# Spectre-Analyzer-SCH_SH2__C.net
KiCad netlist of a schematic drawn in Altium Designer
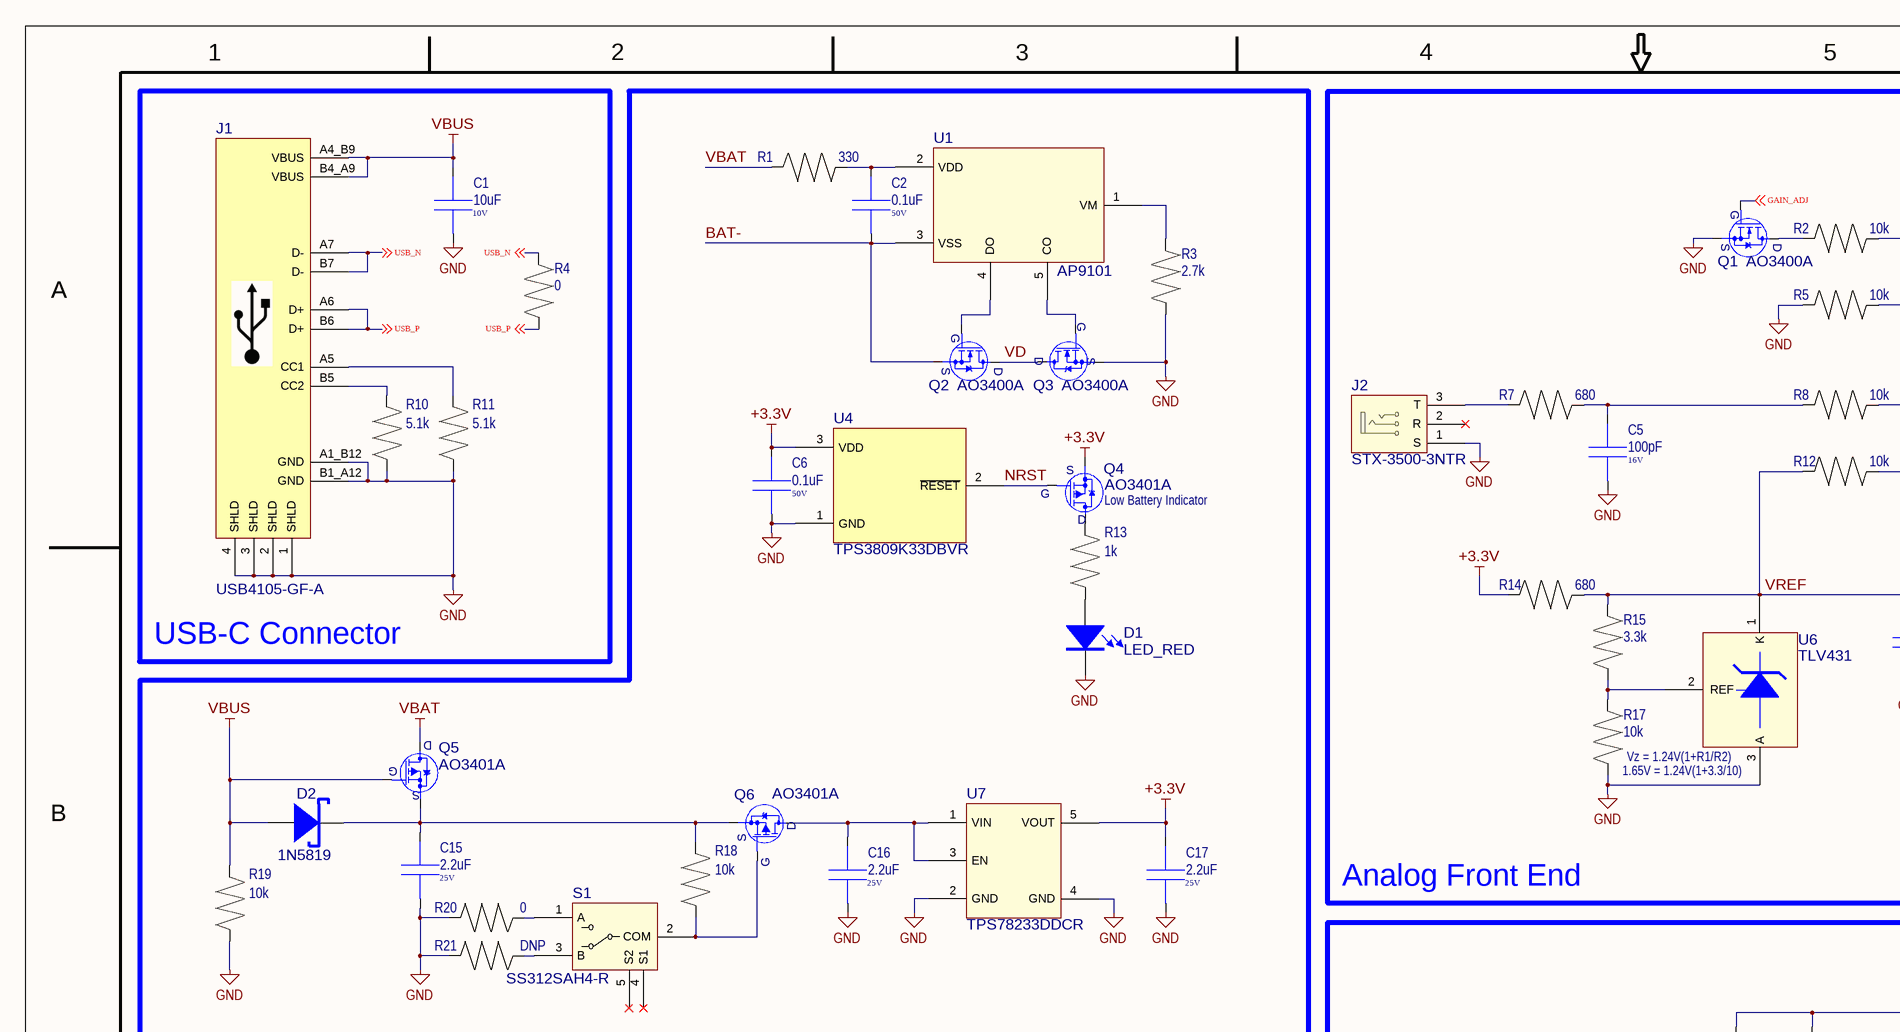
[diagram p0: Spectre-Analyzer-SCH_SH2_(C).SchDoc, top left]
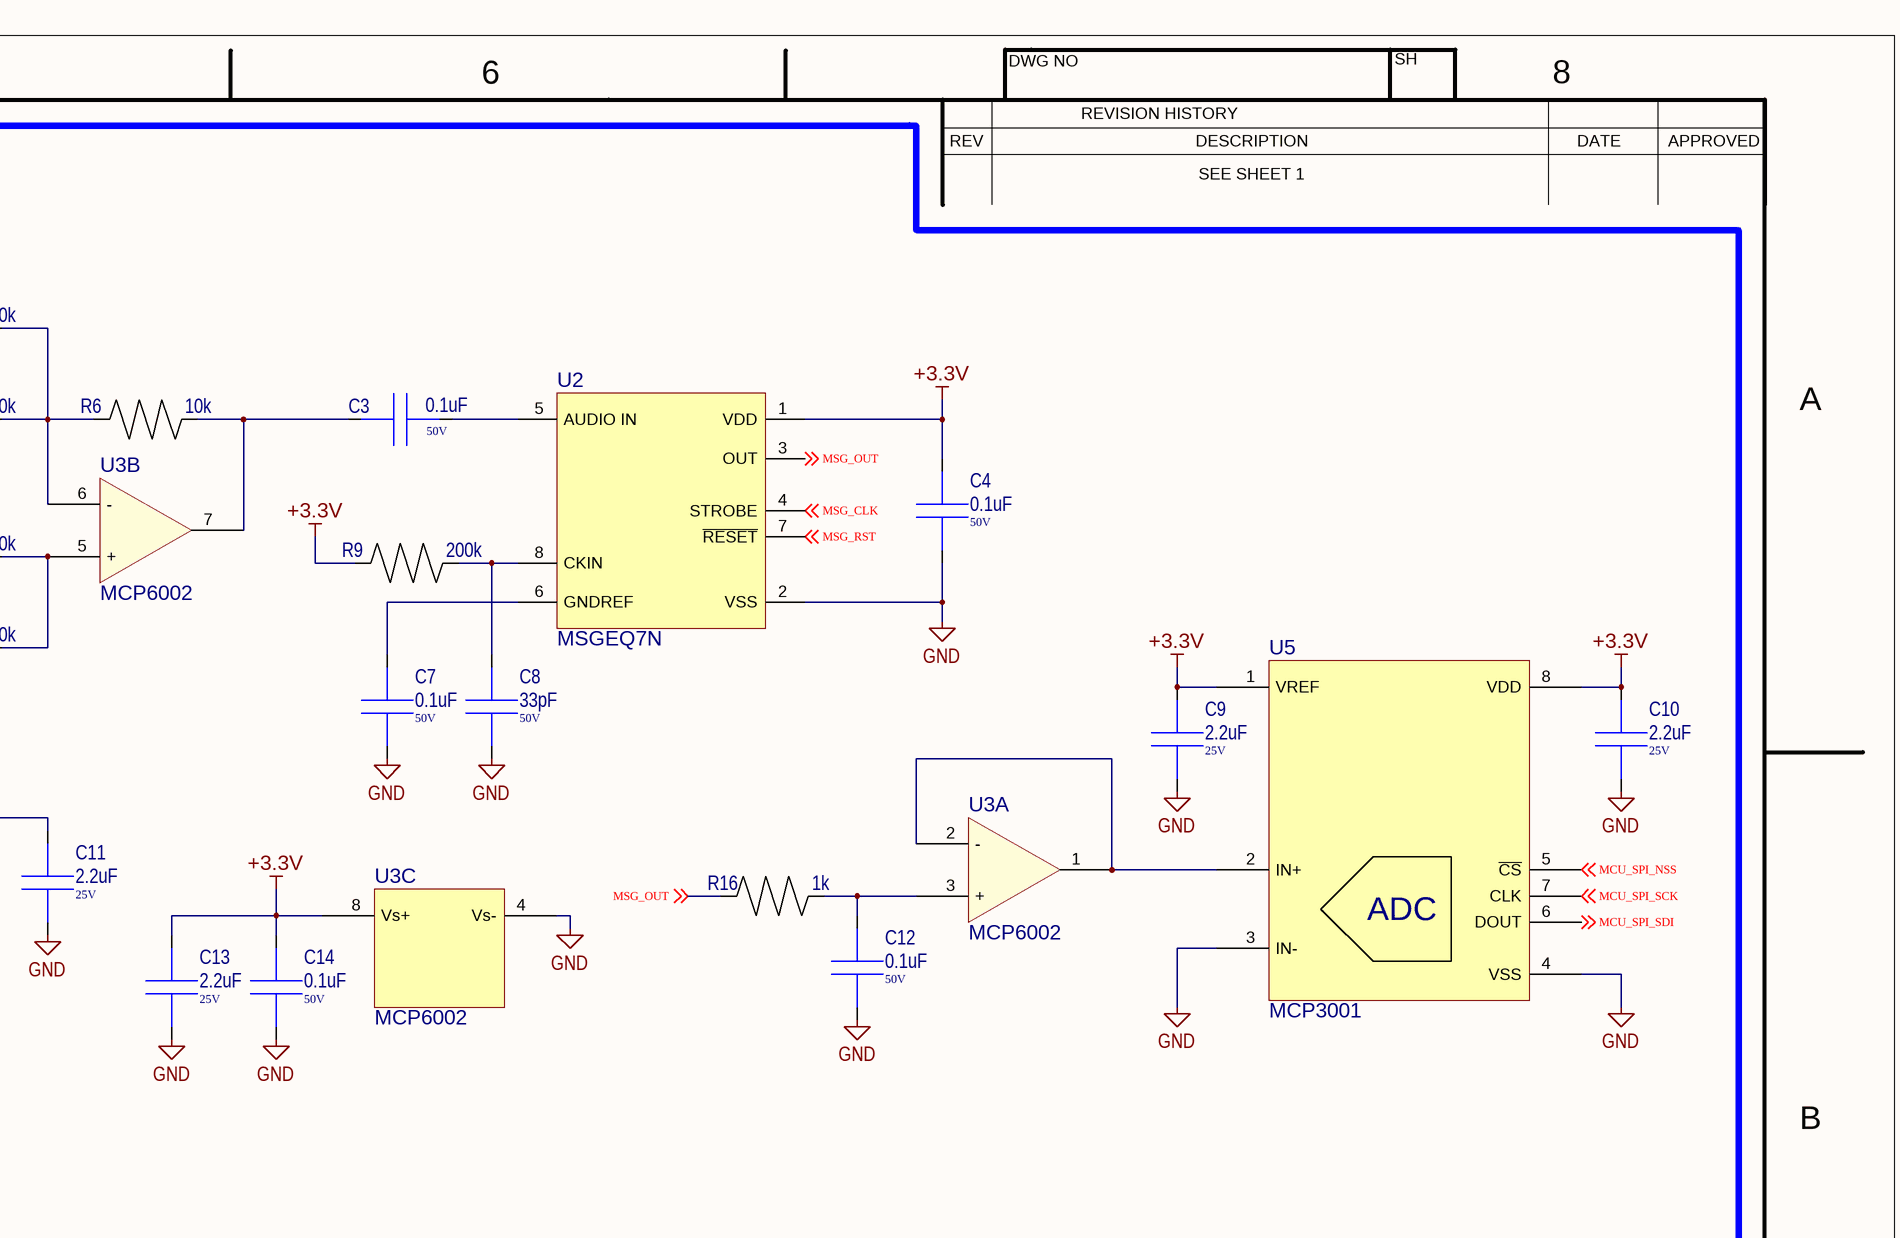
[diagram p1: Spectre-Analyzer-SCH_SH2_(C).SchDoc, top right]
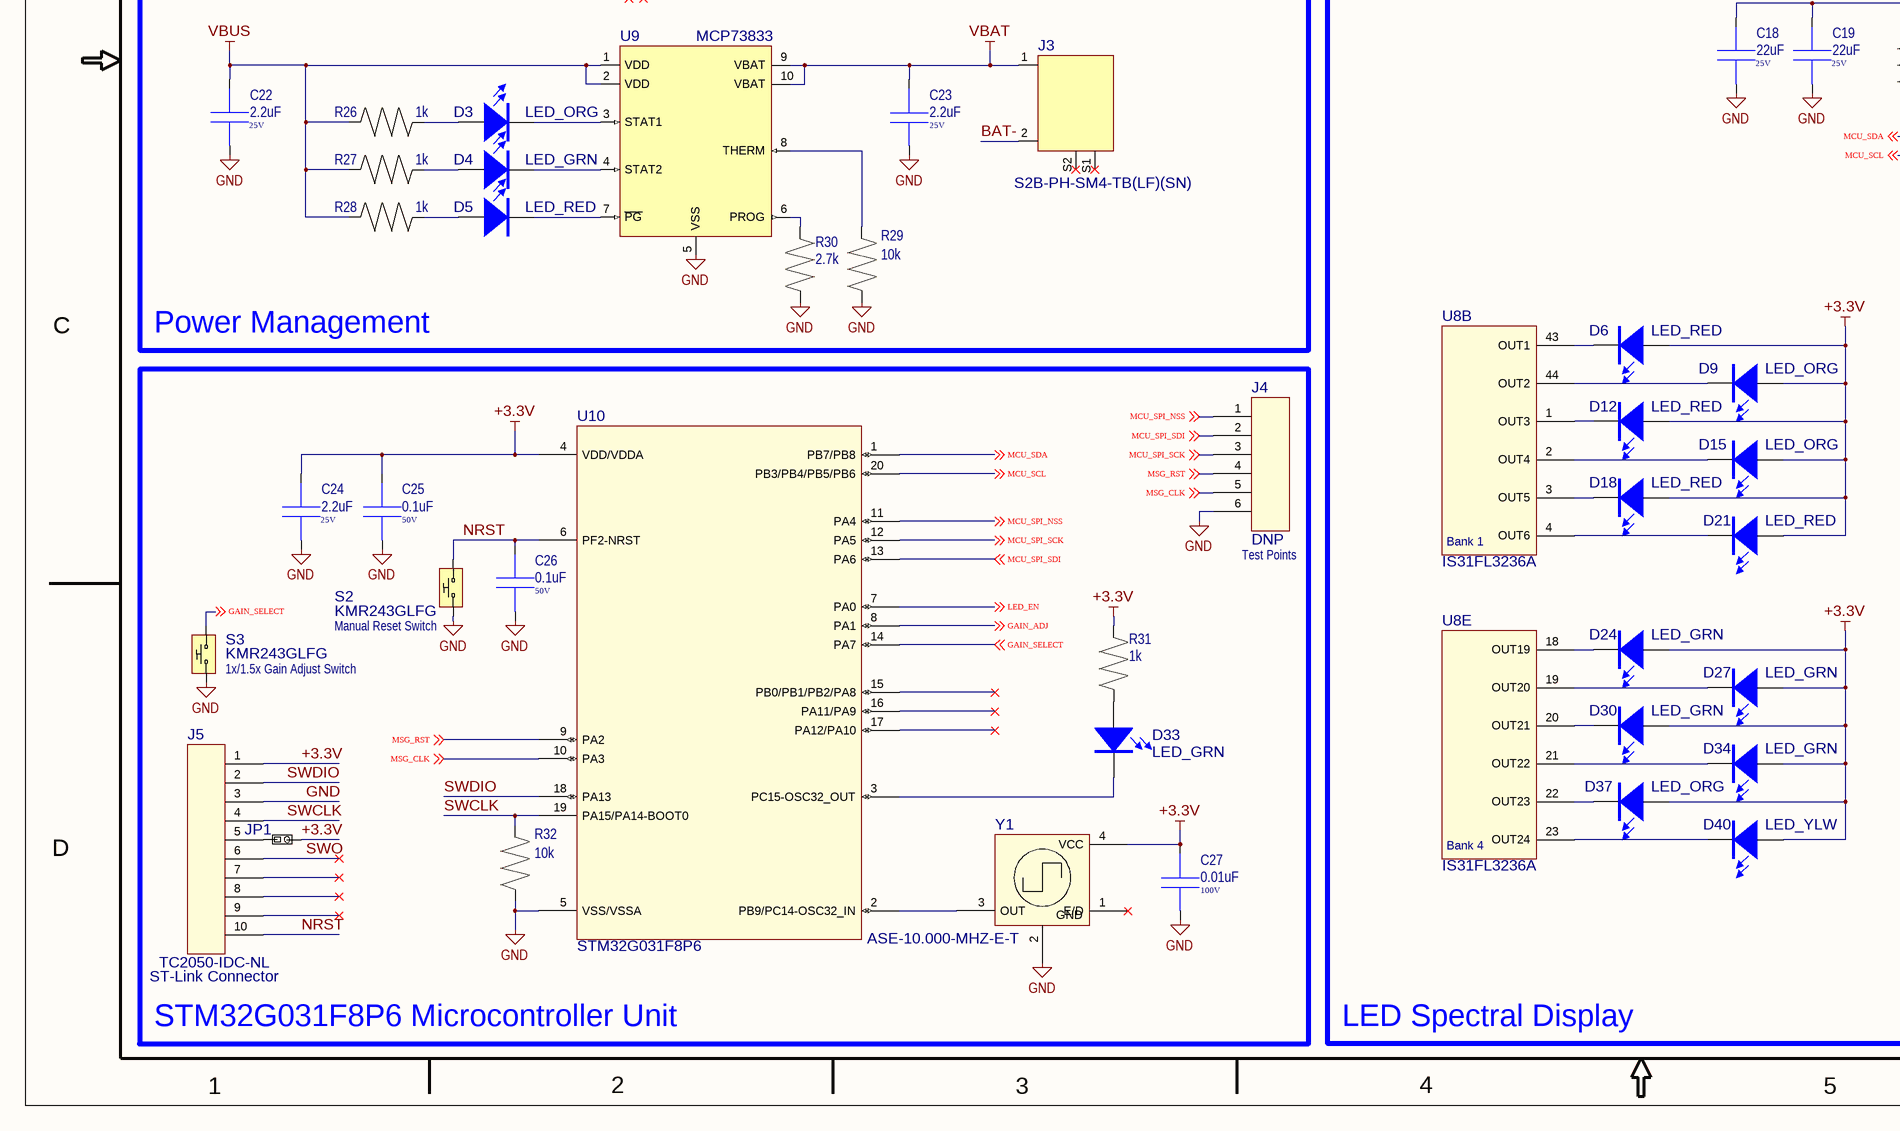
[diagram p2: Spectre-Analyzer-SCH_SH2_(C).SchDoc, bottom left]
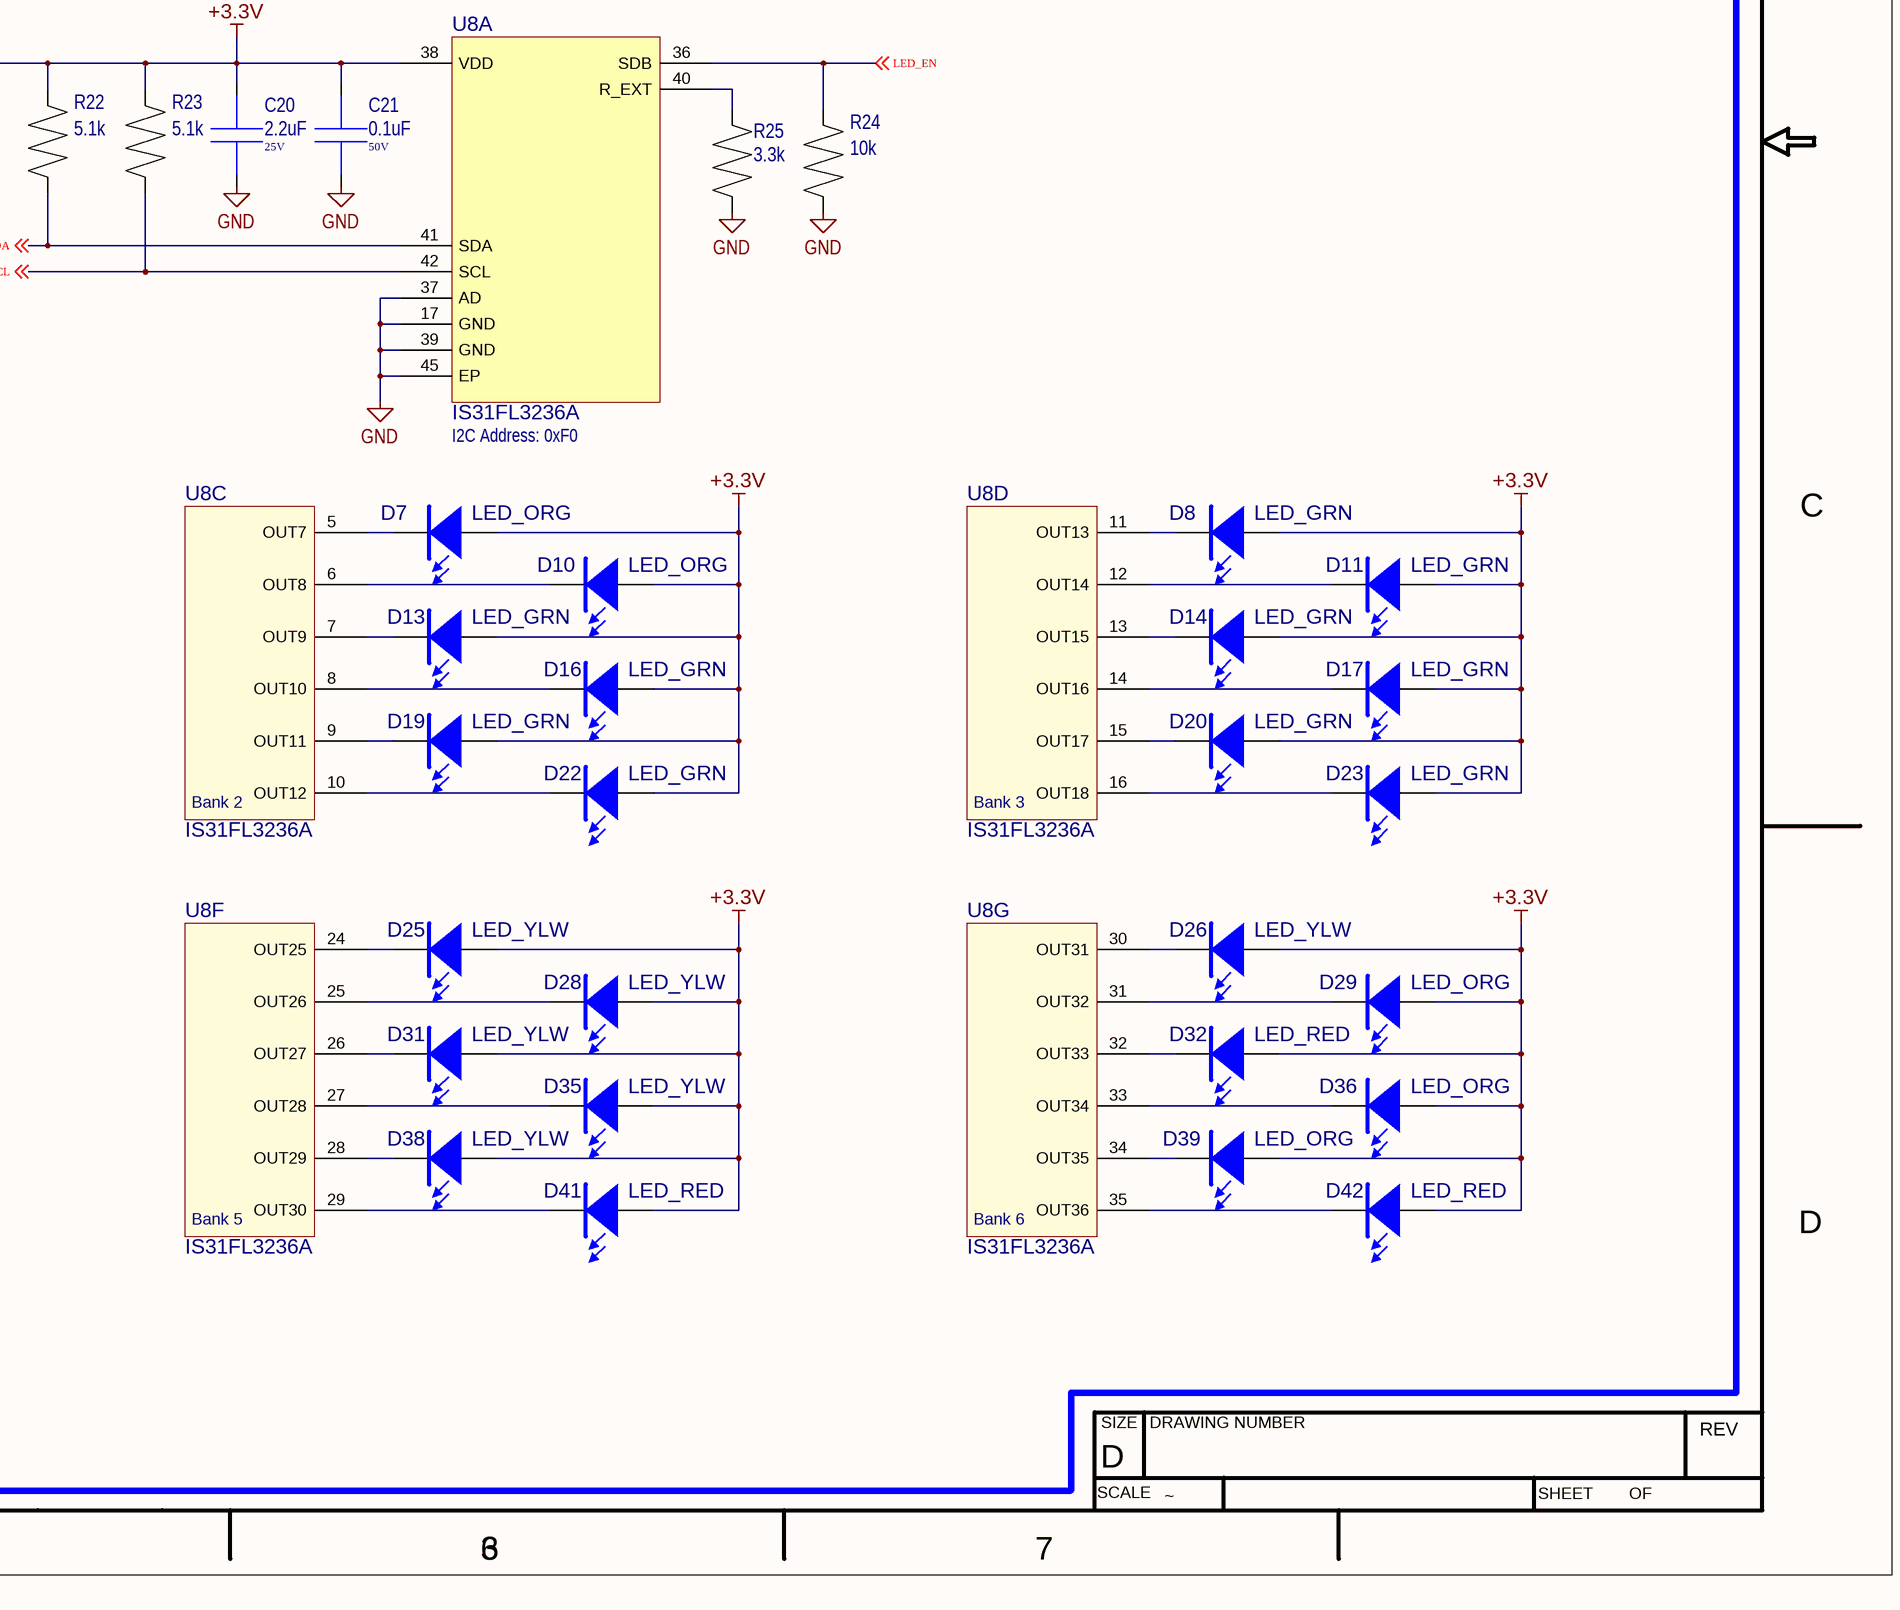
[diagram p3: Spectre-Analyzer-SCH_SH2_(C).SchDoc, bottom right]

(export (version "E")
  (design (tool "Eeschema 10.0.6"))
  (components
    (comp (ref "C1")
      (value "10uF")
      (footprint "0402")
      (description "CAP CER 10UF 10V X5R 0402")
      (fields
        (field (name "PART NUMBER") "CL05A106MP5NUNC")
        (field (name "MANUFACTURER") "Samsung Electro-Mechanics")
        (field (name "VOLTAGE") "10V")
      )
      (libsource (lib "CAPACITORS") (part "CAP"))
    )
    (comp (ref "C2")
      (value "0.1uF")
      (footprint "0402")
      (description "CAP CER 0.1UF 50V X7R 0402")
      (fields
        (field (name "PART NUMBER") "UMK105B7104KVHF")
        (field (name "MANUFACTURER") "Taiyo Yuden")
        (field (name "VOLTAGE") "50V")
      )
      (libsource (lib "CAPACITORS") (part "CAP"))
    )
    (comp (ref "C3")
      (value "0.1uF")
      (footprint "0402")
      (description "CAP CER 0.1UF 50V X7R 0402")
      (fields
        (field (name "PART NUMBER") "UMK105B7104KVHF")
        (field (name "MANUFACTURER") "Taiyo Yuden")
        (field (name "VOLTAGE") "50V")
      )
      (libsource (lib "CAPACITORS") (part "CAP"))
    )
    (comp (ref "C4")
      (value "0.1uF")
      (footprint "0402")
      (description "CAP CER 0.1UF 50V X7R 0402")
      (fields
        (field (name "PART NUMBER") "UMK105B7104KVHF")
        (field (name "MANUFACTURER") "Taiyo Yuden")
        (field (name "VOLTAGE") "50V")
      )
      (libsource (lib "CAPACITORS") (part "CAP"))
    )
    (comp (ref "C5")
      (value "100pF")
      (footprint "0402")
      (description "CAP CER 100PF 16V X7R 0402")
      (fields
        (field (name "PART NUMBER") "VJ0402Y101KXJCW1BC")
        (field (name "MANUFACTURER") "Vishay Vitramon")
        (field (name "VOLTAGE") "16V")
      )
      (libsource (lib "CAPACITORS") (part "CAP"))
    )
    (comp (ref "C6")
      (value "0.1uF")
      (footprint "0402")
      (description "CAP CER 0.1UF 50V X7R 0402")
      (fields
        (field (name "PART NUMBER") "UMK105B7104KVHF")
        (field (name "MANUFACTURER") "Taiyo Yuden")
        (field (name "VOLTAGE") "50V")
      )
      (libsource (lib "CAPACITORS") (part "CAP"))
    )
    (comp (ref "C7")
      (value "0.1uF")
      (footprint "0402")
      (description "CAP CER 0.1UF 50V X7R 0402")
      (fields
        (field (name "PART NUMBER") "UMK105B7104KVHF")
        (field (name "MANUFACTURER") "Taiyo Yuden")
        (field (name "VOLTAGE") "50V")
      )
      (libsource (lib "CAPACITORS") (part "CAP"))
    )
    (comp (ref "C8")
      (value "33pF")
      (footprint "0402")
      (description "CAP CER 33PF 50V X7R 0402")
      (fields
        (field (name "PART NUMBER") "04025C330JAT2A")
        (field (name "MANUFACTURER") "KYOCERA AVX")
        (field (name "VOLTAGE") "50V")
      )
      (libsource (lib "CAPACITORS") (part "CAP"))
    )
    (comp (ref "C9")
      (value "2.2uF")
      (footprint "0402")
      (description "CAP CER 2.2UF 25V X5R 0402")
      (fields
        (field (name "PART NUMBER") "GRM155R61E225KE11D")
        (field (name "MANUFACTURER") "Murata Electronics")
        (field (name "VOLTAGE") "25V")
      )
      (libsource (lib "CAPACITORS") (part "CAP"))
    )
    (comp (ref "C10")
      (value "2.2uF")
      (footprint "0402")
      (description "CAP CER 2.2UF 25V X5R 0402")
      (fields
        (field (name "PART NUMBER") "GRM155R61E225KE11D")
        (field (name "MANUFACTURER") "Murata Electronics")
        (field (name "VOLTAGE") "25V")
      )
      (libsource (lib "CAPACITORS") (part "CAP"))
    )
    (comp (ref "C11")
      (value "2.2uF")
      (footprint "0402")
      (description "CAP CER 2.2UF 25V X5R 0402")
      (fields
        (field (name "PART NUMBER") "GRM155R61E225KE11D")
        (field (name "MANUFACTURER") "Murata Electronics")
        (field (name "VOLTAGE") "25V")
      )
      (libsource (lib "CAPACITORS") (part "CAP"))
    )
    (comp (ref "C12")
      (value "0.1uF")
      (footprint "0402")
      (description "CAP CER 0.1UF 50V X7R 0402")
      (fields
        (field (name "PART NUMBER") "UMK105B7104KVHF")
        (field (name "MANUFACTURER") "Taiyo Yuden")
        (field (name "VOLTAGE") "50V")
      )
      (libsource (lib "CAPACITORS") (part "CAP"))
    )
    (comp (ref "C13")
      (value "2.2uF")
      (footprint "0402")
      (description "CAP CER 2.2UF 25V X5R 0402")
      (fields
        (field (name "PART NUMBER") "GRM155R61E225KE11D")
        (field (name "MANUFACTURER") "Murata Electronics")
        (field (name "VOLTAGE") "25V")
      )
      (libsource (lib "CAPACITORS") (part "CAP"))
    )
    (comp (ref "C14")
      (value "0.1uF")
      (footprint "0402")
      (description "CAP CER 0.1UF 50V X7R 0402")
      (fields
        (field (name "PART NUMBER") "UMK105B7104KVHF")
        (field (name "MANUFACTURER") "Taiyo Yuden")
        (field (name "VOLTAGE") "50V")
      )
      (libsource (lib "CAPACITORS") (part "CAP"))
    )
    (comp (ref "C15")
      (value "2.2uF")
      (footprint "0402")
      (description "CAP CER 2.2UF 25V X5R 0402")
      (fields
        (field (name "PART NUMBER") "GRM155R61E225KE11D")
        (field (name "MANUFACTURER") "Murata Electronics")
        (field (name "VOLTAGE") "25V")
      )
      (libsource (lib "CAPACITORS") (part "CAP"))
    )
    (comp (ref "C16")
      (value "2.2uF")
      (footprint "0402")
      (description "CAP CER 2.2UF 25V X5R 0402")
      (fields
        (field (name "PART NUMBER") "GRM155R61E225KE11D")
        (field (name "MANUFACTURER") "Murata Electronics")
        (field (name "VOLTAGE") "25V")
      )
      (libsource (lib "CAPACITORS") (part "CAP"))
    )
    (comp (ref "C17")
      (value "2.2uF")
      (footprint "0402")
      (description "CAP CER 2.2UF 25V X5R 0402")
      (fields
        (field (name "PART NUMBER") "GRM155R61E225KE11D")
        (field (name "MANUFACTURER") "Murata Electronics")
        (field (name "VOLTAGE") "25V")
      )
      (libsource (lib "CAPACITORS") (part "CAP"))
    )
    (comp (ref "C18")
      (value "22uF")
      (footprint "0805")
      (description "CAP CER 22UF 25V X5R 0805")
      (fields
        (field (name "PART NUMBER") "CL21A226MAYNNNE")
        (field (name "MANUFACTURER") "Samsung Electro-Mechanics")
        (field (name "VOLTAGE") "25V")
      )
      (libsource (lib "CAPACITORS") (part "CAP"))
    )
    (comp (ref "C19")
      (value "22uF")
      (footprint "0805")
      (description "CAP CER 22UF 25V X5R 0805")
      (fields
        (field (name "PART NUMBER") "CL21A226MAYNNNE")
        (field (name "MANUFACTURER") "Samsung Electro-Mechanics")
        (field (name "VOLTAGE") "25V")
      )
      (libsource (lib "CAPACITORS") (part "CAP"))
    )
    (comp (ref "C20")
      (value "2.2uF")
      (footprint "0402")
      (description "CAP CER 2.2UF 25V X5R 0402")
      (fields
        (field (name "PART NUMBER") "GRM155R61E225KE11D")
        (field (name "MANUFACTURER") "Murata Electronics")
        (field (name "VOLTAGE") "25V")
      )
      (libsource (lib "CAPACITORS") (part "CAP"))
    )
    (comp (ref "C21")
      (value "0.1uF")
      (footprint "0402")
      (description "CAP CER 0.1UF 50V X7R 0402")
      (fields
        (field (name "PART NUMBER") "UMK105B7104KVHF")
        (field (name "MANUFACTURER") "Taiyo Yuden")
        (field (name "VOLTAGE") "50V")
      )
      (libsource (lib "CAPACITORS") (part "CAP"))
    )
    (comp (ref "C22")
      (value "2.2uF")
      (footprint "0402")
      (description "CAP CER 2.2UF 25V X5R 0402")
      (fields
        (field (name "PART NUMBER") "GRM155R61E225KE11D")
        (field (name "MANUFACTURER") "Murata Electronics")
        (field (name "VOLTAGE") "25V")
      )
      (libsource (lib "CAPACITORS") (part "CAP"))
    )
    (comp (ref "C23")
      (value "2.2uF")
      (footprint "0402")
      (description "CAP CER 2.2UF 25V X5R 0402")
      (fields
        (field (name "PART NUMBER") "GRM155R61E225KE11D")
        (field (name "MANUFACTURER") "Murata Electronics")
        (field (name "VOLTAGE") "25V")
      )
      (libsource (lib "CAPACITORS") (part "CAP"))
    )
    (comp (ref "C24")
      (value "2.2uF")
      (footprint "0402")
      (description "CAP CER 2.2UF 25V X5R 0402")
      (fields
        (field (name "PART NUMBER") "GRM155R61E225KE11D")
        (field (name "MANUFACTURER") "Murata Electronics")
        (field (name "VOLTAGE") "25V")
      )
      (libsource (lib "CAPACITORS") (part "CAP"))
    )
    (comp (ref "C25")
      (value "0.1uF")
      (footprint "0402")
      (description "CAP CER 0.1UF 50V X7R 0402")
      (fields
        (field (name "PART NUMBER") "UMK105B7104KVHF")
        (field (name "MANUFACTURER") "Taiyo Yuden")
        (field (name "VOLTAGE") "50V")
      )
      (libsource (lib "CAPACITORS") (part "CAP"))
    )
    (comp (ref "C26")
      (value "0.1uF")
      (footprint "0402")
      (description "CAP CER 0.1UF 50V X7R 0402")
      (fields
        (field (name "PART NUMBER") "UMK105B7104KVHF")
        (field (name "MANUFACTURER") "Taiyo Yuden")
        (field (name "VOLTAGE") "50V")
      )
      (libsource (lib "CAPACITORS") (part "CAP"))
    )
    (comp (ref "C27")
      (value "0.01uF")
      (footprint "0402")
      (description "CAP CER 0.01UF 100V X7R 0402")
      (fields
        (field (name "PART NUMBER") "HMR105B7103MV-F")
        (field (name "MANUFACTURER") "Taiyo Yuden")
        (field (name "VOLTAGE") "100V")
      )
      (libsource (lib "CAPACITORS") (part "CAP"))
    )
    (comp (ref "D1")
      (value "LED_RED")
      (footprint "0603_LED_Red")
      (description "Standard LEDs - SMD HE Red 645 nm Water Clear")
      (fields (field (name "PART NUMBER") "KT-0603R") (field (name "MANUFACTURER") "Hubei KENTO Elec"))
      (libsource (lib "SEMICONDUCTORS") (part "LED_Red"))
    )
    (comp (ref "D2")
      (value "1N5819")
      (footprint "SOD-123")
      (description "DIODE SCHOTTKY 40V 1A SOD123")
      (fields (field (name "MANUFACTURER") "Diodes Incorporated") (field (name "PART NUMBER") "1N5819HW-7-F"))
      (libsource (lib "SEMICONDUCTORS") (part "DIODE_SCHOTTKY"))
    )
    (comp (ref "D3")
      (value "LED_ORG")
      (footprint "0603_LED_Red")
      (description "Standard LEDs - SMD HE Orange 598nm~608nm")
      (fields (field (name "PART NUMBER") "SZYY0603O") (field (name "MANUFACTURER") "Yongyu Photoelectric"))
      (libsource (lib "SEMICONDUCTORS") (part "LED_Red"))
    )
    (comp (ref "D4")
      (value "LED_GRN")
      (footprint "0603_LED_Red")
      (description "Standard LEDs - SMD HE Green 518nm Water Clear")
      (fields
        (field (name "PART NUMBER") "19-217/GHC-YR1S2/3T")
        (field (name "MANUFACTURER") "Everlight Elec")
      )
      (libsource (lib "SEMICONDUCTORS") (part "LED_Red"))
    )
    (comp (ref "D5")
      (value "LED_RED")
      (footprint "0603_LED_Red")
      (description "Standard LEDs - SMD HE Red 645 nm Water Clear")
      (fields (field (name "PART NUMBER") "KT-0603R") (field (name "MANUFACTURER") "Hubei KENTO Elec"))
      (libsource (lib "SEMICONDUCTORS") (part "LED_Red"))
    )
    (comp (ref "D6")
      (value "LED_RED")
      (footprint "0603_LED_Red")
      (description "Standard LEDs - SMD HE Red 645 nm Water Clear")
      (fields (field (name "PART NUMBER") "KT-0603R") (field (name "MANUFACTURER") "Hubei KENTO Elec"))
      (libsource (lib "SEMICONDUCTORS") (part "LED_Red"))
    )
    (comp (ref "D7")
      (value "LED_ORG")
      (footprint "0603_LED_Red")
      (description "Standard LEDs - SMD HE Orange 598nm~608nm")
      (fields (field (name "PART NUMBER") "SZYY0603O") (field (name "MANUFACTURER") "Yongyu Photoelectric"))
      (libsource (lib "SEMICONDUCTORS") (part "LED_Red"))
    )
    (comp (ref "D8")
      (value "LED_GRN")
      (footprint "0603_LED_Red")
      (description "Standard LEDs - SMD HE Green 518nm Water Clear")
      (fields
        (field (name "PART NUMBER") "19-217/GHC-YR1S2/3T")
        (field (name "MANUFACTURER") "Everlight Elec")
      )
      (libsource (lib "SEMICONDUCTORS") (part "LED_Red"))
    )
    (comp (ref "D9")
      (value "LED_ORG")
      (footprint "0603_LED_Red")
      (description "Standard LEDs - SMD HE Orange 598nm~608nm")
      (fields (field (name "PART NUMBER") "SZYY0603O") (field (name "MANUFACTURER") "Yongyu Photoelectric"))
      (libsource (lib "SEMICONDUCTORS") (part "LED_Red"))
    )
    (comp (ref "D10")
      (value "LED_ORG")
      (footprint "0603_LED_Red")
      (description "Standard LEDs - SMD HE Orange 598nm~608nm")
      (fields (field (name "PART NUMBER") "SZYY0603O") (field (name "MANUFACTURER") "Yongyu Photoelectric"))
      (libsource (lib "SEMICONDUCTORS") (part "LED_Red"))
    )
    (comp (ref "D11")
      (value "LED_GRN")
      (footprint "0603_LED_Red")
      (description "Standard LEDs - SMD HE Green 518nm Water Clear")
      (fields
        (field (name "PART NUMBER") "19-217/GHC-YR1S2/3T")
        (field (name "MANUFACTURER") "Everlight Elec")
      )
      (libsource (lib "SEMICONDUCTORS") (part "LED_Red"))
    )
    (comp (ref "D12")
      (value "LED_RED")
      (footprint "0603_LED_Red")
      (description "Standard LEDs - SMD HE Red 645 nm Water Clear")
      (fields (field (name "PART NUMBER") "KT-0603R") (field (name "MANUFACTURER") "Hubei KENTO Elec"))
      (libsource (lib "SEMICONDUCTORS") (part "LED_Red"))
    )
    (comp (ref "D13")
      (value "LED_GRN")
      (footprint "0603_LED_Red")
      (description "Standard LEDs - SMD HE Green 518nm Water Clear")
      (fields
        (field (name "PART NUMBER") "19-217/GHC-YR1S2/3T")
        (field (name "MANUFACTURER") "Everlight Elec")
      )
      (libsource (lib "SEMICONDUCTORS") (part "LED_Red"))
    )
    (comp (ref "D14")
      (value "LED_GRN")
      (footprint "0603_LED_Red")
      (description "Standard LEDs - SMD HE Green 518nm Water Clear")
      (fields
        (field (name "PART NUMBER") "19-217/GHC-YR1S2/3T")
        (field (name "MANUFACTURER") "Everlight Elec")
      )
      (libsource (lib "SEMICONDUCTORS") (part "LED_Red"))
    )
    (comp (ref "D15")
      (value "LED_ORG")
      (footprint "0603_LED_Red")
      (description "Standard LEDs - SMD HE Orange 598nm~608nm")
      (fields (field (name "PART NUMBER") "SZYY0603O") (field (name "MANUFACTURER") "Yongyu Photoelectric"))
      (libsource (lib "SEMICONDUCTORS") (part "LED_Red"))
    )
    (comp (ref "D16")
      (value "LED_GRN")
      (footprint "0603_LED_Red")
      (description "Standard LEDs - SMD HE Green 518nm Water Clear")
      (fields
        (field (name "PART NUMBER") "19-217/GHC-YR1S2/3T")
        (field (name "MANUFACTURER") "Everlight Elec")
      )
      (libsource (lib "SEMICONDUCTORS") (part "LED_Red"))
    )
    (comp (ref "D17")
      (value "LED_GRN")
      (footprint "0603_LED_Red")
      (description "Standard LEDs - SMD HE Green 518nm Water Clear")
      (fields
        (field (name "PART NUMBER") "19-217/GHC-YR1S2/3T")
        (field (name "MANUFACTURER") "Everlight Elec")
      )
      (libsource (lib "SEMICONDUCTORS") (part "LED_Red"))
    )
    (comp (ref "D18")
      (value "LED_RED")
      (footprint "0603_LED_Red")
      (description "Standard LEDs - SMD HE Red 645 nm Water Clear")
      (fields (field (name "PART NUMBER") "KT-0603R") (field (name "MANUFACTURER") "Hubei KENTO Elec"))
      (libsource (lib "SEMICONDUCTORS") (part "LED_Red"))
    )
    (comp (ref "D19")
      (value "LED_GRN")
      (footprint "0603_LED_Red")
      (description "Standard LEDs - SMD HE Green 518nm Water Clear")
      (fields
        (field (name "PART NUMBER") "19-217/GHC-YR1S2/3T")
        (field (name "MANUFACTURER") "Everlight Elec")
      )
      (libsource (lib "SEMICONDUCTORS") (part "LED_Red"))
    )
    (comp (ref "D20")
      (value "LED_GRN")
      (footprint "0603_LED_Red")
      (description "Standard LEDs - SMD HE Green 518nm Water Clear")
      (fields
        (field (name "PART NUMBER") "19-217/GHC-YR1S2/3T")
        (field (name "MANUFACTURER") "Everlight Elec")
      )
      (libsource (lib "SEMICONDUCTORS") (part "LED_Red"))
    )
    (comp (ref "D21")
      (value "LED_RED")
      (footprint "0603_LED_Red")
      (description "Standard LEDs - SMD HE Red 645 nm Water Clear")
      (fields (field (name "PART NUMBER") "KT-0603R") (field (name "MANUFACTURER") "Hubei KENTO Elec"))
      (libsource (lib "SEMICONDUCTORS") (part "LED_Red"))
    )
    (comp (ref "D22")
      (value "LED_GRN")
      (footprint "0603_LED_Red")
      (description "Standard LEDs - SMD HE Green 518nm Water Clear")
      (fields
        (field (name "PART NUMBER") "19-217/GHC-YR1S2/3T")
        (field (name "MANUFACTURER") "Everlight Elec")
      )
      (libsource (lib "SEMICONDUCTORS") (part "LED_Red"))
    )
    (comp (ref "D23")
      (value "LED_GRN")
      (footprint "0603_LED_Red")
      (description "Standard LEDs - SMD HE Green 518nm Water Clear")
      (fields
        (field (name "PART NUMBER") "19-217/GHC-YR1S2/3T")
        (field (name "MANUFACTURER") "Everlight Elec")
      )
      (libsource (lib "SEMICONDUCTORS") (part "LED_Red"))
    )
    (comp (ref "D24")
      (value "LED_GRN")
      (footprint "0603_LED_Red")
      (description "Standard LEDs - SMD HE Green 518nm Water Clear")
      (fields
        (field (name "PART NUMBER") "19-217/GHC-YR1S2/3T")
        (field (name "MANUFACTURER") "Everlight Elec")
      )
      (libsource (lib "SEMICONDUCTORS") (part "LED_Red"))
    )
    (comp (ref "D25")
      (value "LED_YLW")
      (footprint "0603_LED_Red")
      (description "Standard LEDs - SMD HE Yellow 585nm Water Clear")
      (fields
        (field (name "PART NUMBER") "19-213/Y2C-CQ2R2L/3T(CY)")
        (field (name "MANUFACTURER") "Everlight Elec")
      )
      (libsource (lib "SEMICONDUCTORS") (part "LED_Red"))
    )
    (comp (ref "D26")
      (value "LED_YLW")
      (footprint "0603_LED_Red")
      (description "Standard LEDs - SMD HE Yellow 585nm Water Clear")
      (fields
        (field (name "PART NUMBER") "19-213/Y2C-CQ2R2L/3T(CY)")
        (field (name "MANUFACTURER") "Everlight Elec")
      )
      (libsource (lib "SEMICONDUCTORS") (part "LED_Red"))
    )
    (comp (ref "D27")
      (value "LED_GRN")
      (footprint "0603_LED_Red")
      (description "Standard LEDs - SMD HE Green 518nm Water Clear")
      (fields
        (field (name "PART NUMBER") "19-217/GHC-YR1S2/3T")
        (field (name "MANUFACTURER") "Everlight Elec")
      )
      (libsource (lib "SEMICONDUCTORS") (part "LED_Red"))
    )
    (comp (ref "D28")
      (value "LED_YLW")
      (footprint "0603_LED_Red")
      (description "Standard LEDs - SMD HE Yellow 585nm Water Clear")
      (fields
        (field (name "PART NUMBER") "19-213/Y2C-CQ2R2L/3T(CY)")
        (field (name "MANUFACTURER") "Everlight Elec")
      )
      (libsource (lib "SEMICONDUCTORS") (part "LED_Red"))
    )
    (comp (ref "D29")
      (value "LED_ORG")
      (footprint "0603_LED_Red")
      (description "Standard LEDs - SMD HE Orange 598nm~608nm")
      (fields (field (name "PART NUMBER") "SZYY0603O") (field (name "MANUFACTURER") "Yongyu Photoelectric"))
      (libsource (lib "SEMICONDUCTORS") (part "LED_Red"))
    )
    (comp (ref "D30")
      (value "LED_GRN")
      (footprint "0603_LED_Red")
      (description "Standard LEDs - SMD HE Red 645 nm Water Clear")
      (fields
        (field (name "PART NUMBER") "19-213/Y2C-CQ2R2L/3T(CY)")
        (field (name "MANUFACTURER") "Everlight Elec")
      )
      (libsource (lib "SEMICONDUCTORS") (part "LED_Red"))
    )
    (comp (ref "D31")
      (value "LED_YLW")
      (footprint "0603_LED_Red")
      (description "Standard LEDs - SMD HE Yellow 585nm Water Clear")
      (fields
        (field (name "PART NUMBER") "19-213/Y2C-CQ2R2L/3T(CY)")
        (field (name "MANUFACTURER") "Everlight Elec")
      )
      (libsource (lib "SEMICONDUCTORS") (part "LED_Red"))
    )
    (comp (ref "D32")
      (value "LED_RED")
      (footprint "0603_LED_Red")
      (description "Standard LEDs - SMD HE Red 645 nm Water Clear")
      (fields (field (name "PART NUMBER") "KT-0603R") (field (name "MANUFACTURER") "Hubei KENTO Elec"))
      (libsource (lib "SEMICONDUCTORS") (part "LED_Red"))
    )
    (comp (ref "D33")
      (value "LED_GRN")
      (footprint "0603_LED_Red")
      (description "Standard LEDs - SMD HE Green 518nm Water Clear")
      (fields
        (field (name "PART NUMBER") "19-217/GHC-YR1S2/3T")
        (field (name "MANUFACTURER") "Everlight Elec")
      )
      (libsource (lib "SEMICONDUCTORS") (part "LED_Red"))
    )
    (comp (ref "D34")
      (value "LED_GRN")
      (footprint "0603_LED_Red")
      (description "Standard LEDs - SMD HE Green 518nm Water Clear")
      (fields
        (field (name "PART NUMBER") "19-217/GHC-YR1S2/3T")
        (field (name "MANUFACTURER") "Everlight Elec")
      )
      (libsource (lib "SEMICONDUCTORS") (part "LED_Red"))
    )
    (comp (ref "D35")
      (value "LED_YLW")
      (footprint "0603_LED_Red")
      (description "Standard LEDs - SMD HE Yellow 585nm Water Clear")
      (fields
        (field (name "PART NUMBER") "19-213/Y2C-CQ2R2L/3T(CY)")
        (field (name "MANUFACTURER") "Everlight Elec")
      )
      (libsource (lib "SEMICONDUCTORS") (part "LED_Red"))
    )
    (comp (ref "D36")
      (value "LED_ORG")
      (footprint "0603_LED_Red")
      (description "Standard LEDs - SMD HE Orange 598nm~608nm")
      (fields (field (name "PART NUMBER") "SZYY0603O") (field (name "MANUFACTURER") "Yongyu Photoelectric"))
      (libsource (lib "SEMICONDUCTORS") (part "LED_Red"))
    )
    (comp (ref "D37")
      (value "LED_ORG")
      (footprint "0603_LED_Red")
      (description "Standard LEDs - SMD HE Orange 598nm~608nm")
      (fields (field (name "PART NUMBER") "SZYY0603O") (field (name "MANUFACTURER") "Yongyu Photoelectric"))
      (libsource (lib "SEMICONDUCTORS") (part "LED_Red"))
    )
    (comp (ref "D38")
      (value "LED_YLW")
      (footprint "0603_LED_Red")
      (description "Standard LEDs - SMD HE Yellow 585nm Water Clear")
      (fields
        (field (name "PART NUMBER") "19-213/Y2C-CQ2R2L/3T(CY)")
        (field (name "MANUFACTURER") "Everlight Elec")
      )
      (libsource (lib "SEMICONDUCTORS") (part "LED_Red"))
    )
    (comp (ref "D39")
      (value "LED_ORG")
      (footprint "0603_LED_Red")
      (description "Standard LEDs - SMD HE Orange 598nm~608nm")
      (fields (field (name "PART NUMBER") "SZYY0603O") (field (name "MANUFACTURER") "Yongyu Photoelectric"))
      (libsource (lib "SEMICONDUCTORS") (part "LED_Red"))
    )
    (comp (ref "D40")
      (value "LED_YLW")
      (footprint "0603_LED_Red")
      (description "Standard LEDs - SMD HE Yellow 585nm Water Clear")
      (fields
        (field (name "PART NUMBER") "19-213/Y2C-CQ2R2L/3T(CY)")
        (field (name "MANUFACTURER") "Everlight Elec")
      )
      (libsource (lib "SEMICONDUCTORS") (part "LED_Red"))
    )
    (comp (ref "D41")
      (value "LED_RED")
      (footprint "0603_LED_Red")
      (description "Standard LEDs - SMD HE Red 645 nm Water Clear")
      (fields (field (name "PART NUMBER") "KT-0603R") (field (name "MANUFACTURER") "Hubei KENTO Elec"))
      (libsource (lib "SEMICONDUCTORS") (part "LED_Red"))
    )
    (comp (ref "D42")
      (value "LED_RED")
      (footprint "0603_LED_Red")
      (description "Standard LEDs - SMD HE Red 645 nm Water Clear")
      (fields (field (name "PART NUMBER") "KT-0603R") (field (name "MANUFACTURER") "Hubei KENTO Elec"))
      (libsource (lib "SEMICONDUCTORS") (part "LED_Red"))
    )
    (comp (ref "J1")
      (value "USB4105-GF-A")
      (footprint "USB4105-GF-A")
      (description "CONN RCP USB2.0 TYP C 24P SMD RA")
      (fields (field (name "MANUFACTURER") "GCT"))
      (libsource (lib "Connectors") (part "USB4105-GF-A"))
    )
    (comp (ref "J2")
      (value "STX-3500-3NTR")
      (footprint "STX-3500-3NTR")
      (description "CONN JACK STEREO 3.5MM SMD R/A")
      (fields (field (name "MANUFACTURER") "Kycon, Inc."))
      (libsource (lib "ConnectorLib") (part "STX-3500-3NTR"))
    )
    (comp (ref "J3")
      (value "S2B-PH-SM4-TB(LF)(SN)")
      (footprint "S2B-PH-SM4-TB(LF)(SN)")
      (description "CONN HEADER SMD R/A 2POS 2MM")
      (fields (field (name "MANUFACTURER") "JST Sales America Inc."))
      (libsource (lib "ConnectorLib") (part "S2B-PH-SM4-TB(LF)(SN)"))
    )
    (comp (ref "J4")
      (value "DNP")
      (footprint "801-43-006-10-012000")
      (description "CONN SOCKET STRIP 6 POS 0.1\"")
      (fields (field (name "MANUFACTURER") "Mill-Max") (field (name "PART NUMBER") "801-43-006-10-012000"))
      (libsource (lib "ConnectorLib") (part "801-43-006-10-012000"))
    )
    (comp (ref "J5")
      (value "TC2050-IDC-NL")
      (footprint "TC2050-IDC-NL-FP")
      (description "CBL PLUG-OF-NAILS 10-PIN")
      (fields (field (name "MANUFACTURER") "Tag-Connect LLC"))
      (libsource (lib "Connectors") (part "TC2050-IDC-NL"))
    )
    (comp (ref "JP1")
      (value "Solder Jumper")
      (footprint "SOLDER JUMPER")
      (description "Solder Jumper Single 0.5mm Pitch")
      (libsource (lib "ConnectorLib") (part "SolderJumper_Single"))
    )
    (comp (ref "Q1")
      (value "AO3400A")
      (footprint "SOT-23-3")
      (description "MOSFET N-CH 30V 5.7A SOT23-3L")
      (fields (field (name "MANUFACTURER") "Alpha & Omega Semiconductor Inc."))
      (libsource (lib "") (part "MOSFET_N_1"))
    )
    (comp (ref "Q2")
      (value "AO3400A")
      (footprint "SOT-23-3")
      (description "MOSFET N-CH 30V 5.7A SOT23-3L")
      (fields (field (name "MANUFACTURER") "Alpha & Omega Semiconductor Inc."))
      (libsource (lib "") (part "MOSFET_N_1"))
    )
    (comp (ref "Q3")
      (value "AO3400A")
      (footprint "SOT-23-3")
      (description "MOSFET N-CH 30V 5.7A SOT23-3L")
      (fields (field (name "MANUFACTURER") "Alpha & Omega Semiconductor Inc."))
      (libsource (lib "SEMICONDUCTORS") (part "MOSFET_N"))
    )
    (comp (ref "Q4")
      (value "AO3401A")
      (footprint "SOT-23")
      (description "MOSFET P-CH 30V 4A SOT23-3L")
      (fields (field (name "MANUFACTURER") "Alpha & Omega Semiconductor Inc."))
      (libsource (lib "") (part "MOSFET_P_1"))
    )
    (comp (ref "Q5")
      (value "AO3401A")
      (footprint "SOT-23")
      (description "MOSFET P-CH 30V 4A SOT23-3L")
      (fields (field (name "MANUFACTURER") "Alpha & Omega Semiconductor Inc."))
      (libsource (lib "") (part "MOSFET_P_2"))
    )
    (comp (ref "Q6")
      (value "AO3401A")
      (footprint "SOT-23")
      (description "MOSFET P-CH 30V 4A SOT23-3L")
      (fields (field (name "MANUFACTURER") "Alpha & Omega Semiconductor Inc."))
      (libsource (lib "SEMICONDUCTORS") (part "MOSFET_P"))
    )
    (comp (ref "R1")
      (value "330")
      (footprint "0402")
      (description "RES 330 OHM 1% 1/16W 0402")
      (fields (field (name "PART NUMBER") "CR0402AFX-3300GLF") (field (name "MANUFACTURER") "Bourns"))
      (libsource (lib "RESISTORS") (part "RES"))
    )
    (comp (ref "R2")
      (value "10k")
      (footprint "0402")
      (description "RES SMD 10K OHM 1% 1/16W 0402")
      (fields (field (name "PART NUMBER") "CR0402-FX-1002GLF") (field (name "MANUFACTURER") "Bourns"))
      (libsource (lib "RESISTORS") (part "RES"))
    )
    (comp (ref "R3")
      (value "2.7k")
      (footprint "0402")
      (description "RES SMD 2.7K OHM 1% 1/16W 0402")
      (fields (field (name "PART NUMBER") "CR0402-FX-2701GLF") (field (name "MANUFACTURER") "Bourns"))
      (libsource (lib "RESISTORS") (part "RES"))
    )
    (comp (ref "R4")
      (value "0")
      (footprint "0402")
      (description "Thick Film Resistors - SMD 1/16watt 0ohm Commercial Use")
      (fields (field (name "PART NUMBER") "CRCW04020000Z0EDC") (field (name "MANUFACTURER") "Vishay / Dale"))
      (libsource (lib "RESISTORS") (part "RES"))
    )
    (comp (ref "R5")
      (value "10k")
      (footprint "0402")
      (description "RES SMD 10K OHM 1% 1/16W 0402")
      (fields (field (name "PART NUMBER") "CR0402-FX-1002GLF") (field (name "MANUFACTURER") "Bourns"))
      (libsource (lib "RESISTORS") (part "RES"))
    )
    (comp (ref "R6")
      (value "10k")
      (footprint "0402")
      (description "RES SMD 10K OHM 1% 1/16W 0402")
      (fields (field (name "PART NUMBER") "CR0402-FX-1002GLF") (field (name "MANUFACTURER") "Bourns"))
      (libsource (lib "RESISTORS") (part "RES"))
    )
    (comp (ref "R7")
      (value "680")
      (footprint "0402")
      (description "RES SMD 680 OHM 1% 1/16W 0402")
      (fields (field (name "PART NUMBER") "CR0402-FX-6800GLF") (field (name "MANUFACTURER") "Bourns"))
      (libsource (lib "RESISTORS") (part "RES"))
    )
    (comp (ref "R8")
      (value "10k")
      (footprint "0402")
      (description "RES SMD 10K OHM 1% 1/16W 0402")
      (fields (field (name "PART NUMBER") "CR0402-FX-1002GLF") (field (name "MANUFACTURER") "Bourns"))
      (libsource (lib "RESISTORS") (part "RES"))
    )
    (comp (ref "R9")
      (value "200k")
      (footprint "0402")
      (description "RES SMD 200K OHM 1% 1/16W 0402")
      (fields (field (name "PART NUMBER") "CR0402-FX-2003GLF") (field (name "MANUFACTURER") "Bourns"))
      (libsource (lib "RESISTORS") (part "RES"))
    )
    (comp (ref "R10")
      (value "5.1k")
      (footprint "0402")
      (description "RES SMD 5.1K OHM 1% 1/16W 0402")
      (fields (field (name "PART NUMBER") "CRCW04025K10FKED") (field (name "MANUFACTURER") "Vishay / Dale"))
      (libsource (lib "RESISTORS") (part "RES"))
    )
    (comp (ref "R11")
      (value "5.1k")
      (footprint "0402")
      (description "RES SMD 5.1K OHM 1% 1/16W 0402")
      (fields (field (name "PART NUMBER") "CRCW04025K10FKED") (field (name "MANUFACTURER") "Vishay / Dale"))
      (libsource (lib "RESISTORS") (part "RES"))
    )
    (comp (ref "R12")
      (value "10k")
      (footprint "0402")
      (description "RES SMD 10K OHM 1% 1/16W 0402")
      (fields (field (name "PART NUMBER") "CR0402-FX-1002GLF") (field (name "MANUFACTURER") "Bourns"))
      (libsource (lib "RESISTORS") (part "RES"))
    )
    (comp (ref "R13")
      (value "1k")
      (footprint "0402")
      (description "RES SMD 1K OHM 1% 1/16W 0402")
      (fields (field (name "PART NUMBER") "CR0402-FX-1001GLF") (field (name "MANUFACTURER") "Bourns"))
      (libsource (lib "RESISTORS") (part "RES"))
    )
    (comp (ref "R14")
      (value "680")
      (footprint "0402")
      (description "RES SMD 680 OHM 1% 1/16W 0402")
      (fields (field (name "PART NUMBER") "CR0402-FX-6800GLF") (field (name "MANUFACTURER") "Bourns"))
      (libsource (lib "RESISTORS") (part "RES"))
    )
    (comp (ref "R15")
      (value "3.3k")
      (footprint "0402")
      (description "RES SMD 3.3K OHM 1% 1/16W 0402")
      (fields (field (name "PART NUMBER") "CR0402-FX-3301GLF") (field (name "MANUFACTURER") "Bourns"))
      (libsource (lib "RESISTORS") (part "RES"))
    )
    (comp (ref "R16")
      (value "1k")
      (footprint "0402")
      (description "RES 1K OHM 1% 1/16W 0402")
      (fields (field (name "PART NUMBER") "CR0402AFX-1001GLF") (field (name "MANUFACTURER") "Bourns"))
      (libsource (lib "RESISTORS") (part "RES"))
    )
    (comp (ref "R17")
      (value "10k")
      (footprint "0402")
      (description "RES SMD 10K OHM 1% 1/16W 0402")
      (fields (field (name "PART NUMBER") "CR0402-FX-1002GLF") (field (name "MANUFACTURER") "Bourns"))
      (libsource (lib "RESISTORS") (part "RES"))
    )
    (comp (ref "R18")
      (value "10k")
      (footprint "0402")
      (description "RES SMD 10K OHM 1% 1/16W 0402")
      (fields (field (name "PART NUMBER") "CR0402-FX-1002GLF") (field (name "MANUFACTURER") "Bourns"))
      (libsource (lib "RESISTORS") (part "RES"))
    )
    (comp (ref "R19")
      (value "10k")
      (footprint "0402")
      (description "RES SMD 10K OHM 1% 1/16W 0402")
      (fields (field (name "PART NUMBER") "CR0402-FX-1002GLF") (field (name "MANUFACTURER") "Bourns"))
      (libsource (lib "RESISTORS") (part "RES"))
    )
    (comp (ref "R20")
      (value "0")
      (footprint "0402")
      (description "Thick Film Resistors - SMD 1/16watt 0ohm Commercial Use")
      (fields (field (name "PART NUMBER") "CRCW04020000Z0EDC") (field (name "MANUFACTURER") "Vishay / Dale"))
      (libsource (lib "RESISTORS") (part "RES"))
    )
    (comp (ref "R21")
      (value "DNP")
      (footprint "0402")
      (description "Thick Film Resistors - SMD 1/16watt 0ohm Commercial Use")
      (fields (field (name "PART NUMBER") "CRCW04020000Z0EDC") (field (name "MANUFACTURER") "Vishay / Dale"))
      (libsource (lib "RESISTORS") (part "RES"))
    )
    (comp (ref "R22")
      (value "5.1k")
      (footprint "0402")
      (description "RES SMD 5.1K OHM 1% 1/16W 0402")
      (fields (field (name "PART NUMBER") "CRCW04025K10FKED") (field (name "MANUFACTURER") "Vishay / Dale"))
      (libsource (lib "RESISTORS") (part "RES"))
    )
    (comp (ref "R23")
      (value "5.1k")
      (footprint "0402")
      (description "RES SMD 5.1K OHM 1% 1/16W 0402")
      (fields (field (name "PART NUMBER") "CRCW04025K10FKED") (field (name "MANUFACTURER") "Vishay / Dale"))
      (libsource (lib "RESISTORS") (part "RES"))
    )
    (comp (ref "R24")
      (value "10k")
      (footprint "0402")
      (description "RES SMD 10K OHM 1% 1/16W 0402")
      (fields (field (name "PART NUMBER") "CR0402-FX-1002GLF") (field (name "MANUFACTURER") "Bourns"))
      (libsource (lib "RESISTORS") (part "RES"))
    )
    (comp (ref "R25")
      (value "3.3k")
      (footprint "0402")
      (description "RES SMD 3.3K OHM 1% 1/16W 0402")
      (fields (field (name "PART NUMBER") "CR0402-FX-3301GLF") (field (name "MANUFACTURER") "Bourns"))
      (libsource (lib "RESISTORS") (part "RES"))
    )
    (comp (ref "R26")
      (value "1k")
      (footprint "0402")
      (description "RES 1K OHM 1% 1/16W 0402")
      (fields (field (name "PART NUMBER") "CR0402AFX-1001GLF") (field (name "MANUFACTURER") "Bourns"))
      (libsource (lib "RESISTORS") (part "RES"))
    )
    (comp (ref "R27")
      (value "1k")
      (footprint "0402")
      (description "RES 1K OHM 1% 1/16W 0402")
      (fields (field (name "PART NUMBER") "CR0402AFX-1001GLF") (field (name "MANUFACTURER") "Bourns"))
      (libsource (lib "RESISTORS") (part "RES"))
    )
    (comp (ref "R28")
      (value "1k")
      (footprint "0402")
      (description "RES 1K OHM 1% 1/16W 0402")
      (fields (field (name "PART NUMBER") "CR0402AFX-1001GLF") (field (name "MANUFACTURER") "Bourns"))
      (libsource (lib "RESISTORS") (part "RES"))
    )
    (comp (ref "R29")
      (value "10k")
      (footprint "0402")
      (description "RES SMD 10K OHM 1% 1/16W 0402")
      (fields (field (name "PART NUMBER") "CR0402-FX-1002GLF") (field (name "MANUFACTURER") "Bourns"))
      (libsource (lib "RESISTORS") (part "RES"))
    )
    (comp (ref "R30")
      (value "2.7k")
      (footprint "0402")
      (description "RES SMD 2.7K OHM 1% 1/16W 0402")
      (fields (field (name "PART NUMBER") "CR0402-FX-2701GLF") (field (name "MANUFACTURER") "Bourns"))
      (libsource (lib "RESISTORS") (part "RES"))
    )
    (comp (ref "R31")
      (value "1k")
      (footprint "0402")
      (description "RES 1K OHM 1% 1/16W 0402")
      (fields (field (name "PART NUMBER") "CR0402AFX-1001GLF") (field (name "MANUFACTURER") "Bourns"))
      (libsource (lib "RESISTORS") (part "RES"))
    )
    (comp (ref "R32")
      (value "10k")
      (footprint "0402")
      (description "RES SMD 10K OHM 1% 1/16W 0402")
      (fields (field (name "PART NUMBER") "CR0402-FX-1002GLF") (field (name "MANUFACTURER") "Bourns"))
      (libsource (lib "RESISTORS") (part "RES"))
    )
    (comp (ref "S1")
      (value "SS312SAH4-R")
      (footprint "SW_SS312SAH4-R")
      (description "SWITCH SLIDE SPDT 0.4VA 28V")
      (fields (field (name "MANUFACTURER") "NKK Switches"))
      (libsource (lib "Switches") (part "SS312SAH4-R"))
    )
    (comp (ref "S2")
      (value "KMR243GLFG")
      (footprint "KMR 2 Series")
      (description "SWITCH TACTILE SPST-NO 0.01A 32V")
      (fields (field (name "MANUFACTURER") "C&K"))
      (libsource (lib "SwitchesLib") (part "KMR 2 Series"))
    )
    (comp (ref "S3")
      (value "KMR243GLFG")
      (footprint "KMR 2 Series")
      (description "SWITCH TACTILE SPST-NO 0.01A 32V")
      (fields (field (name "MANUFACTURER") "C&K"))
      (libsource (lib "SwitchesLib") (part "KMR 2 Series"))
    )
    (comp (ref "U1")
      (value "AP9101")
      (footprint "TSOT23-5")
      (description "IC BATT PROT LI-ION 1CELL SOT25")
      (fields
        (field (name "MANUFACTURER") "Diodes Incorporated")
        (field (name "PART NUMBER") "AP9101CAK-AKTRG1")
      )
      (libsource (lib "Linear Regulators") (part "AP9101CAK-AKTRG1"))
    )
    (comp (ref "U2")
      (value "MSGEQ7N")
      (footprint "SOIC-8")
      (description "SWITCHED CAPA AUDIO ANALYZER SOIC-8")
      (fields (field (name "MANUFACTURER") "Mixed Signal Integrated"))
      (libsource (lib "Sensors") (part "MSGEQ7"))
    )
    (comp (ref "U3")
      (value "MCP6002")
      (footprint "SOIC-8")
      (description "IC OPAMP GP 2 CIRCUIT 8SOIC")
      (fields
        (field (name "PART NUMBER") "MCP6002-E/SN")
        (field (name "MANUFACTURER") "Microchip Technology")
      )
      (libsource (lib "Operational Amplifiers") (part "AD8072"))
    )
    (comp (ref "U4")
      (value "TPS3809K33DBVR")
      (footprint "SOT-23-3")
      (description "IC SUPERVISOR 1 CHANNEL SOT23-3")
      (fields (field (name "MANUFACTURER") "Texas Instruments"))
      (libsource (lib "Sensors") (part "TPS3809x"))
    )
    (comp (ref "U5")
      (value "MCP3001")
      (footprint "SOIC-8")
      (description "IC ADC 10BIT SAR 8SOIC")
      (fields
        (field (name "MANUFACTURER") "Microchip Technology")
        (field (name "PART NUMBER") "MCP3001T-I/SN")
      )
      (libsource (lib "Data_Converters") (part "MCP3001"))
    )
    (comp (ref "U6")
      (value "TLV431")
      (footprint "SOT-23-3")
      (description "IC VREF SHUNT ADJ SOT23-3")
      (fields (field (name "MANUFACTURER") "onsemi") (field (name "PART NUMBER") "TLV431ASN1T1G"))
      (libsource (lib "Linear Regulators") (part "TL431xxDBZR"))
    )
    (comp (ref "U7")
      (value "TPS78233DDCR")
      (footprint "TSOT23-5")
      (description "IC REG LINEAR 3.3V 150MA SOT23-5")
      (fields (field (name "MANUFACTURER") "Texas Instruments"))
      (libsource (lib "Linear Regulators") (part "TPS782xxDDCR"))
    )
    (comp (ref "U8")
      (value "IS31FL3236A")
      (footprint "QFN-44 5x5")
      (description "IC LED DRIVER LINEAR 38MA 44QFN")
      (fields
        (field (name "MANUFACTURER") "Lumissil Microsystems")
        (field (name "PART NUMBER") "IS31FL3236A-QFLS2-TR")
      )
      (libsource (lib "LED Drivers") (part "IS31FL3236A"))
    )
    (comp (ref "U9")
      (value "MCP73833")
      (footprint "MSOP-10")
      (description "IC BATT CNTRL LI-ION 1CEL 10MSOP")
      (fields (field (name "PART NUMBER") "MCP73833-CNI/UN") (field (name "MANUFACTURER") "Microchip"))
      (libsource (lib "Linear Regulators") (part "MCP73833"))
    )
    (comp (ref "U10")
      (value "STM32G031F8P6")
      (footprint "TSSOP-20")
      (description "IC MCU 32BIT 64KB FLASH 20TSSOP")
      (fields (field (name "MANUFACTURER") "STMicroelectronics"))
      (libsource (lib "MicrocontrollerUnits") (part "STM32G031FxP6"))
    )
    (comp (ref "Y1")
      (value "ASE-10.000-MHZ-E-T")
      (footprint "ASE-XXXXX-X-X-X")
      (description "OSC XO 10.000MHZ CMOS SMD")
      (fields (field (name "MANUFACTURER") "Abracon"))
      (libsource (lib "Oscillators") (part "ASE-XXXXX-MHZ-X-X"))
    )
  )
  (nets
    (net (code "1") (name "+3.3V") (class "Default")
      (node (ref "C10") (pin "2") (pinfunction "2_2") (pintype "passive"))
      (node (ref "C13") (pin "2") (pinfunction "2_2") (pintype "passive"))
      (node (ref "C14") (pin "2") (pinfunction "2_2") (pintype "passive"))
      (node (ref "C17") (pin "2") (pinfunction "2_2") (pintype "passive"))
      (node (ref "C18") (pin "2") (pinfunction "2_2") (pintype "passive"))
      (node (ref "C19") (pin "2") (pinfunction "2_2") (pintype "passive"))
      (node (ref "C20") (pin "2") (pinfunction "2_2") (pintype "passive"))
      (node (ref "C21") (pin "2") (pinfunction "2_2") (pintype "passive"))
      (node (ref "C24") (pin "2") (pinfunction "2_2") (pintype "passive"))
      (node (ref "C25") (pin "2") (pinfunction "2_2") (pintype "passive"))
      (node (ref "C27") (pin "2") (pinfunction "2_2") (pintype "passive"))
      (node (ref "C4") (pin "2") (pinfunction "2_2") (pintype "passive"))
      (node (ref "C6") (pin "2") (pinfunction "2_2") (pintype "passive"))
      (node (ref "C9") (pin "2") (pinfunction "2_2") (pintype "passive"))
      (node (ref "D10") (pin "1") (pinfunction "A_1") (pintype "passive"))
      (node (ref "D11") (pin "1") (pinfunction "A_1") (pintype "passive"))
      (node (ref "D12") (pin "1") (pinfunction "A_1") (pintype "passive"))
      (node (ref "D13") (pin "1") (pinfunction "A_1") (pintype "passive"))
      (node (ref "D14") (pin "1") (pinfunction "A_1") (pintype "passive"))
      (node (ref "D15") (pin "1") (pinfunction "A_1") (pintype "passive"))
      (node (ref "D16") (pin "1") (pinfunction "A_1") (pintype "passive"))
      (node (ref "D17") (pin "1") (pinfunction "A_1") (pintype "passive"))
      (node (ref "D18") (pin "1") (pinfunction "A_1") (pintype "passive"))
      (node (ref "D19") (pin "1") (pinfunction "A_1") (pintype "passive"))
      (node (ref "D20") (pin "1") (pinfunction "A_1") (pintype "passive"))
      (node (ref "D21") (pin "1") (pinfunction "A_1") (pintype "passive"))
      (node (ref "D22") (pin "1") (pinfunction "A_1") (pintype "passive"))
      (node (ref "D23") (pin "1") (pinfunction "A_1") (pintype "passive"))
      (node (ref "D24") (pin "1") (pinfunction "A_1") (pintype "passive"))
      (node (ref "D25") (pin "1") (pinfunction "A_1") (pintype "passive"))
      (node (ref "D26") (pin "1") (pinfunction "A_1") (pintype "passive"))
      (node (ref "D27") (pin "1") (pinfunction "A_1") (pintype "passive"))
      (node (ref "D28") (pin "1") (pinfunction "A_1") (pintype "passive"))
      (node (ref "D29") (pin "1") (pinfunction "A_1") (pintype "passive"))
      (node (ref "D30") (pin "1") (pinfunction "A_1") (pintype "passive"))
      (node (ref "D31") (pin "1") (pinfunction "A_1") (pintype "passive"))
      (node (ref "D32") (pin "1") (pinfunction "A_1") (pintype "passive"))
      (node (ref "D34") (pin "1") (pinfunction "A_1") (pintype "passive"))
      (node (ref "D35") (pin "1") (pinfunction "A_1") (pintype "passive"))
      (node (ref "D36") (pin "1") (pinfunction "A_1") (pintype "passive"))
      (node (ref "D37") (pin "1") (pinfunction "A_1") (pintype "passive"))
      (node (ref "D38") (pin "1") (pinfunction "A_1") (pintype "passive"))
      (node (ref "D39") (pin "1") (pinfunction "A_1") (pintype "passive"))
      (node (ref "D40") (pin "1") (pinfunction "A_1") (pintype "passive"))
      (node (ref "D41") (pin "1") (pinfunction "A_1") (pintype "passive"))
      (node (ref "D42") (pin "1") (pinfunction "A_1") (pintype "passive"))
      (node (ref "D6") (pin "1") (pinfunction "A_1") (pintype "passive"))
      (node (ref "D7") (pin "1") (pinfunction "A_1") (pintype "passive"))
      (node (ref "D8") (pin "1") (pinfunction "A_1") (pintype "passive"))
      (node (ref "D9") (pin "1") (pinfunction "A_1") (pintype "passive"))
      (node (ref "J5") (pin "1") (pinfunction "1_1") (pintype "passive"))
      (node (ref "JP1") (pin "2") (pinfunction "2_2") (pintype "passive"))
      (node (ref "Q4") (pin "3") (pinfunction "S_3") (pintype "passive"))
      (node (ref "R14") (pin "1") (pinfunction "1_1") (pintype "passive"))
      (node (ref "R22") (pin "2") (pinfunction "2_2") (pintype "passive"))
      (node (ref "R23") (pin "2") (pinfunction "2_2") (pintype "passive"))
      (node (ref "R31") (pin "2") (pinfunction "2_2") (pintype "passive"))
      (node (ref "R9") (pin "1") (pinfunction "1_1") (pintype "passive"))
      (node (ref "U10") (pin "4") (pinfunction "VDD/VDDA_4") (pintype "power_in"))
      (node (ref "U2") (pin "1") (pinfunction "VDD_1") (pintype "passive"))
      (node (ref "U3") (pin "8") (pinfunction "Vs+_8") (pintype "power_in"))
      (node (ref "U4") (pin "3") (pinfunction "VDD_3") (pintype "passive"))
      (node (ref "U5") (pin "1") (pinfunction "VREF_1") (pintype "passive"))
      (node (ref "U5") (pin "8") (pinfunction "VDD_8") (pintype "passive"))
      (node (ref "U7") (pin "5") (pinfunction "VOUT_5") (pintype "passive"))
      (node (ref "U8") (pin "38") (pinfunction "VDD_38") (pintype "passive"))
      (node (ref "Y1") (pin "4") (pinfunction "VCC_4") (pintype "power_in"))
    )
    (net (code "2") (name "/BAT-") (class "Default")
      (node (ref "C2") (pin "1") (pinfunction "1_1") (pintype "passive"))
      (node (ref "J3") (pin "2") (pinfunction "2_2") (pintype "passive"))
      (node (ref "Q2") (pin "3") (pinfunction "S_3") (pintype "passive"))
      (node (ref "U1") (pin "3") (pinfunction "VSS_3") (pintype "passive"))
    )
    (net (code "3") (name "/NRST") (class "Default")
      (node (ref "C26") (pin "2") (pinfunction "2_2") (pintype "passive"))
      (node (ref "J5") (pin "10") (pinfunction "10_10") (pintype "passive"))
      (node (ref "Q4") (pin "1") (pinfunction "G_1") (pintype "passive"))
      (node (ref "S2") (pin "2") (pinfunction "2_2") (pintype "passive"))
      (node (ref "U10") (pin "6") (pinfunction "PF2-NRST_6") (pintype "passive"))
      (node (ref "U4") (pin "2") (pinfunction "~{RESET}_2") (pintype "passive"))
    )
    (net (code "4") (name "/SWCLK") (class "Default")
      (node (ref "J5") (pin "4") (pinfunction "4_4") (pintype "passive"))
      (node (ref "R32") (pin "2") (pinfunction "2_2") (pintype "passive"))
      (node (ref "U10") (pin "19") (pinfunction "PA15/PA14-BOOT0_19") (pintype "passive"))
    )
    (net (code "5") (name "/SWDIO") (class "Default")
      (node (ref "J5") (pin "2") (pinfunction "2_2") (pintype "passive"))
      (node (ref "U10") (pin "18") (pinfunction "PA13_18") (pintype "bidirectional"))
    )
    (net (code "6") (name "/SWO") (class "Default")
      (node (ref "J5") (pin "6") (pinfunction "6_6") (pintype "passive+no_connect"))
    )
    (net (code "7") (name "/VD") (class "Default")
      (node (ref "Q2") (pin "2") (pinfunction "D_2") (pintype "passive"))
      (node (ref "Q3") (pin "2") (pinfunction "D_2") (pintype "passive"))
    )
    (net (code "8") (name "/VREF") (class "Default")
      (node (ref "C11") (pin "2") (pinfunction "2_2") (pintype "passive"))
      (node (ref "R12") (pin "1") (pinfunction "1_1") (pintype "passive"))
      (node (ref "R14") (pin "2") (pinfunction "2_2") (pintype "passive"))
      (node (ref "R15") (pin "1") (pinfunction "1_1") (pintype "passive"))
      (node (ref "U6") (pin "1") (pinfunction "K_1") (pintype "passive"))
    )
    (net (code "9") (name "GAIN_ADJ") (class "Default")
      (node (ref "Q1") (pin "1") (pinfunction "G_1") (pintype "passive"))
      (node (ref "U10") (pin "8") (pinfunction "PA1_8") (pintype "bidirectional"))
    )
    (net (code "10") (name "GAIN_SELECT") (class "Default")
      (node (ref "S3") (pin "2") (pinfunction "2_2") (pintype "passive"))
      (node (ref "U10") (pin "14") (pinfunction "PA7_14") (pintype "bidirectional"))
    )
    (net (code "11") (name "GND") (class "Default")
      (node (ref "C1") (pin "1") (pinfunction "1_1") (pintype "passive"))
      (node (ref "C10") (pin "1") (pinfunction "1_1") (pintype "passive"))
      (node (ref "C11") (pin "1") (pinfunction "1_1") (pintype "passive"))
      (node (ref "C12") (pin "1") (pinfunction "1_1") (pintype "passive"))
      (node (ref "C13") (pin "1") (pinfunction "1_1") (pintype "passive"))
      (node (ref "C14") (pin "1") (pinfunction "1_1") (pintype "passive"))
      (node (ref "C15") (pin "1") (pinfunction "1_1") (pintype "passive"))
      (node (ref "C16") (pin "1") (pinfunction "1_1") (pintype "passive"))
      (node (ref "C17") (pin "1") (pinfunction "1_1") (pintype "passive"))
      (node (ref "C18") (pin "1") (pinfunction "1_1") (pintype "passive"))
      (node (ref "C19") (pin "1") (pinfunction "1_1") (pintype "passive"))
      (node (ref "C20") (pin "1") (pinfunction "1_1") (pintype "passive"))
      (node (ref "C21") (pin "1") (pinfunction "1_1") (pintype "passive"))
      (node (ref "C22") (pin "1") (pinfunction "1_1") (pintype "passive"))
      (node (ref "C23") (pin "1") (pinfunction "1_1") (pintype "passive"))
      (node (ref "C24") (pin "1") (pinfunction "1_1") (pintype "passive"))
      (node (ref "C25") (pin "1") (pinfunction "1_1") (pintype "passive"))
      (node (ref "C26") (pin "1") (pinfunction "1_1") (pintype "passive"))
      (node (ref "C27") (pin "1") (pinfunction "1_1") (pintype "passive"))
      (node (ref "C4") (pin "1") (pinfunction "1_1") (pintype "passive"))
      (node (ref "C5") (pin "1") (pinfunction "1_1") (pintype "passive"))
      (node (ref "C6") (pin "1") (pinfunction "1_1") (pintype "passive"))
      (node (ref "C7") (pin "1") (pinfunction "1_1") (pintype "passive"))
      (node (ref "C8") (pin "1") (pinfunction "1_1") (pintype "passive"))
      (node (ref "C9") (pin "1") (pinfunction "1_1") (pintype "passive"))
      (node (ref "D1") (pin "2") (pinfunction "K_2") (pintype "passive"))
      (node (ref "J1") (pin "1") (pinfunction "SHLD_1") (pintype "passive"))
      (node (ref "J1") (pin "2") (pinfunction "SHLD_2") (pintype "passive"))
      (node (ref "J1") (pin "3") (pinfunction "SHLD_3") (pintype "passive"))
      (node (ref "J1") (pin "4") (pinfunction "SHLD_4") (pintype "passive"))
      (node (ref "J1") (pin "A1_B12") (pinfunction "GND_A1_B12") (pintype "passive"))
      (node (ref "J1") (pin "B1_A12") (pinfunction "GND_B1_A12") (pintype "passive"))
      (node (ref "J2") (pin "1") (pinfunction "S_1") (pintype "power_in"))
      (node (ref "J4") (pin "6") (pinfunction "6_6") (pintype "passive"))
      (node (ref "J5") (pin "3") (pinfunction "3_3") (pintype "passive"))
      (node (ref "Q1") (pin "3") (pinfunction "S_3") (pintype "passive"))
      (node (ref "Q3") (pin "3") (pinfunction "S_3") (pintype "passive"))
      (node (ref "R10") (pin "1") (pinfunction "1_1") (pintype "passive"))
      (node (ref "R11") (pin "1") (pinfunction "1_1") (pintype "passive"))
      (node (ref "R17") (pin "2") (pinfunction "2_2") (pintype "passive"))
      (node (ref "R19") (pin "1") (pinfunction "1_1") (pintype "passive"))
      (node (ref "R20") (pin "2") (pinfunction "2_2") (pintype "passive"))
      (node (ref "R21") (pin "2") (pinfunction "2_2") (pintype "passive"))
      (node (ref "R24") (pin "1") (pinfunction "1_1") (pintype "passive"))
      (node (ref "R25") (pin "2") (pinfunction "2_2") (pintype "passive"))
      (node (ref "R29") (pin "1") (pinfunction "1_1") (pintype "passive"))
      (node (ref "R3") (pin "2") (pinfunction "2_2") (pintype "passive"))
      (node (ref "R30") (pin "2") (pinfunction "2_2") (pintype "passive"))
      (node (ref "R32") (pin "1") (pinfunction "1_1") (pintype "passive"))
      (node (ref "R5") (pin "1") (pinfunction "1_1") (pintype "passive"))
      (node (ref "S2") (pin "1") (pinfunction "1_1") (pintype "passive"))
      (node (ref "S3") (pin "1") (pinfunction "1_1") (pintype "passive"))
      (node (ref "U10") (pin "5") (pinfunction "VSS/VSSA_5") (pintype "power_in"))
      (node (ref "U2") (pin "2") (pinfunction "VSS_2") (pintype "power_in"))
      (node (ref "U3") (pin "4") (pinfunction "Vs-_4") (pintype "power_in"))
      (node (ref "U4") (pin "1") (pinfunction "GND_1") (pintype "passive"))
      (node (ref "U5") (pin "3") (pinfunction "IN-_3") (pintype "passive"))
      (node (ref "U5") (pin "4") (pinfunction "VSS_4") (pintype "power_in"))
      (node (ref "U6") (pin "3") (pinfunction "A_3") (pintype "passive"))
      (node (ref "U7") (pin "2") (pinfunction "GND_2") (pintype "passive"))
      (node (ref "U7") (pin "4") (pinfunction "GND_4") (pintype "passive"))
      (node (ref "U8") (pin "17") (pinfunction "GND_17") (pintype "passive"))
      (node (ref "U8") (pin "37") (pinfunction "AD_37") (pintype "passive"))
      (node (ref "U8") (pin "39") (pinfunction "GND_39") (pintype "passive"))
      (node (ref "U8") (pin "45") (pinfunction "EP_45") (pintype "passive"))
      (node (ref "U9") (pin "5") (pinfunction "VSS_5") (pintype "power_in"))
      (node (ref "Y1") (pin "2") (pinfunction "GND_2") (pintype "passive"))
    )
    (net (code "12") (name "LED_EN") (class "Default")
      (node (ref "R24") (pin "2") (pinfunction "2_2") (pintype "passive"))
      (node (ref "U10") (pin "7") (pinfunction "PA0_7") (pintype "bidirectional"))
      (node (ref "U8") (pin "36") (pinfunction "SDB_36") (pintype "passive"))
    )
    (net (code "13") (name "MCU_SCL") (class "Default")
      (node (ref "R23") (pin "1") (pinfunction "1_1") (pintype "passive"))
      (node (ref "U10") (pin "20") (pinfunction "PB3/PB4/PB5/PB6_20") (pintype "bidirectional"))
      (node (ref "U8") (pin "42") (pinfunction "SCL_42") (pintype "passive"))
    )
    (net (code "14") (name "MCU_SDA") (class "Default")
      (node (ref "R22") (pin "1") (pinfunction "1_1") (pintype "passive"))
      (node (ref "U10") (pin "1") (pinfunction "PB7/PB8_1") (pintype "bidirectional"))
      (node (ref "U8") (pin "41") (pinfunction "SDA_41") (pintype "passive"))
    )
    (net (code "15") (name "MCU_SPI_NSS") (class "Default")
      (node (ref "J4") (pin "1") (pinfunction "1_1") (pintype "passive"))
      (node (ref "U10") (pin "11") (pinfunction "PA4_11") (pintype "bidirectional"))
      (node (ref "U5") (pin "5") (pinfunction "~{CS}_5") (pintype "passive"))
    )
    (net (code "16") (name "MCU_SPI_SCK") (class "Default")
      (node (ref "J4") (pin "3") (pinfunction "3_3") (pintype "passive"))
      (node (ref "U10") (pin "12") (pinfunction "PA5_12") (pintype "bidirectional"))
      (node (ref "U5") (pin "7") (pinfunction "CLK_7") (pintype "passive"))
    )
    (net (code "17") (name "MCU_SPI_SDI") (class "Default")
      (node (ref "J4") (pin "2") (pinfunction "2_2") (pintype "passive"))
      (node (ref "U10") (pin "13") (pinfunction "PA6_13") (pintype "bidirectional"))
      (node (ref "U5") (pin "6") (pinfunction "DOUT_6") (pintype "passive"))
    )
    (net (code "18") (name "MSG_CLK") (class "Default")
      (node (ref "J4") (pin "5") (pinfunction "5_5") (pintype "passive"))
      (node (ref "U10") (pin "10") (pinfunction "PA3_10") (pintype "bidirectional"))
      (node (ref "U2") (pin "4") (pinfunction "STROBE_4") (pintype "passive"))
    )
    (net (code "19") (name "MSG_OUT") (class "Default")
      (node (ref "R16") (pin "1") (pinfunction "1_1") (pintype "passive"))
      (node (ref "U2") (pin "3") (pinfunction "OUT_3") (pintype "passive"))
    )
    (net (code "20") (name "MSG_RST") (class "Default")
      (node (ref "J4") (pin "4") (pinfunction "4_4") (pintype "passive"))
      (node (ref "U10") (pin "9") (pinfunction "PA2_9") (pintype "bidirectional"))
      (node (ref "U2") (pin "7") (pinfunction "~{RESET}_7") (pintype "passive"))
    )
    (net (code "21") (name "Net-(C5-Pad2)") (class "Default")
      (node (ref "C5") (pin "2") (pinfunction "2_2") (pintype "passive"))
      (node (ref "R7") (pin "2") (pinfunction "2_2") (pintype "passive"))
      (node (ref "R8") (pin "1") (pinfunction "1_1") (pintype "passive"))
    )
    (net (code "22") (name "Net-(D1-A)") (class "Default")
      (node (ref "D1") (pin "1") (pinfunction "A_1") (pintype "passive"))
      (node (ref "R13") (pin "1") (pinfunction "1_1") (pintype "passive"))
    )
    (net (code "23") (name "Net-(D2-K)") (class "Default")
      (node (ref "C15") (pin "2") (pinfunction "2_2") (pintype "passive"))
      (node (ref "D2") (pin "2") (pinfunction "K_2") (pintype "passive"))
      (node (ref "Q5") (pin "3") (pinfunction "S_3") (pintype "passive"))
      (node (ref "Q6") (pin "3") (pinfunction "S_3") (pintype "passive"))
      (node (ref "R18") (pin "2") (pinfunction "2_2") (pintype "passive"))
    )
    (net (code "24") (name "Net-(D3-A)") (class "Default")
      (node (ref "D3") (pin "1") (pinfunction "A_1") (pintype "passive"))
      (node (ref "R26") (pin "2") (pinfunction "2_2") (pintype "passive"))
    )
    (net (code "25") (name "Net-(D3-K)") (class "Default")
      (node (ref "D3") (pin "2") (pinfunction "K_2") (pintype "passive"))
      (node (ref "U9") (pin "3") (pinfunction "STAT1_3") (pintype "input"))
    )
    (net (code "26") (name "Net-(D4-A)") (class "Default")
      (node (ref "D4") (pin "1") (pinfunction "A_1") (pintype "passive"))
      (node (ref "R27") (pin "2") (pinfunction "2_2") (pintype "passive"))
    )
    (net (code "27") (name "Net-(D4-K)") (class "Default")
      (node (ref "D4") (pin "2") (pinfunction "K_2") (pintype "passive"))
      (node (ref "U9") (pin "4") (pinfunction "STAT2_4") (pintype "input"))
    )
    (net (code "28") (name "Net-(D5-A)") (class "Default")
      (node (ref "D5") (pin "1") (pinfunction "A_1") (pintype "passive"))
      (node (ref "R28") (pin "2") (pinfunction "2_2") (pintype "passive"))
    )
    (net (code "29") (name "Net-(D5-K)") (class "Default")
      (node (ref "D5") (pin "2") (pinfunction "K_2") (pintype "passive"))
      (node (ref "U9") (pin "7") (pinfunction "~{PG}_7") (pintype "input"))
    )
    (net (code "30") (name "Net-(D6-K)") (class "Default")
      (node (ref "D6") (pin "2") (pinfunction "K_2") (pintype "passive"))
      (node (ref "U8") (pin "43") (pinfunction "OUT1_43") (pintype "passive"))
    )
    (net (code "31") (name "Net-(D7-K)") (class "Default")
      (node (ref "D7") (pin "2") (pinfunction "K_2") (pintype "passive"))
      (node (ref "U8") (pin "5") (pinfunction "OUT7_5") (pintype "passive"))
    )
    (net (code "32") (name "Net-(D8-K)") (class "Default")
      (node (ref "D8") (pin "2") (pinfunction "K_2") (pintype "passive"))
      (node (ref "U8") (pin "11") (pinfunction "OUT13_11") (pintype "passive"))
    )
    (net (code "33") (name "Net-(D9-K)") (class "Default")
      (node (ref "D9") (pin "2") (pinfunction "K_2") (pintype "passive"))
      (node (ref "U8") (pin "44") (pinfunction "OUT2_44") (pintype "passive"))
    )
    (net (code "34") (name "Net-(D10-K)") (class "Default")
      (node (ref "D10") (pin "2") (pinfunction "K_2") (pintype "passive"))
      (node (ref "U8") (pin "6") (pinfunction "OUT8_6") (pintype "passive"))
    )
    (net (code "35") (name "Net-(D11-K)") (class "Default")
      (node (ref "D11") (pin "2") (pinfunction "K_2") (pintype "passive"))
      (node (ref "U8") (pin "12") (pinfunction "OUT14_12") (pintype "passive"))
    )
    (net (code "36") (name "Net-(D12-K)") (class "Default")
      (node (ref "D12") (pin "2") (pinfunction "K_2") (pintype "passive"))
      (node (ref "U8") (pin "1") (pinfunction "OUT3_1") (pintype "passive"))
    )
    (net (code "37") (name "Net-(D13-K)") (class "Default")
      (node (ref "D13") (pin "2") (pinfunction "K_2") (pintype "passive"))
      (node (ref "U8") (pin "7") (pinfunction "OUT9_7") (pintype "passive"))
    )
    (net (code "38") (name "Net-(D14-K)") (class "Default")
      (node (ref "D14") (pin "2") (pinfunction "K_2") (pintype "passive"))
      (node (ref "U8") (pin "13") (pinfunction "OUT15_13") (pintype "passive"))
    )
    (net (code "39") (name "Net-(D15-K)") (class "Default")
      (node (ref "D15") (pin "2") (pinfunction "K_2") (pintype "passive"))
      (node (ref "U8") (pin "2") (pinfunction "OUT4_2") (pintype "passive"))
    )
    (net (code "40") (name "Net-(D16-K)") (class "Default")
      (node (ref "D16") (pin "2") (pinfunction "K_2") (pintype "passive"))
      (node (ref "U8") (pin "8") (pinfunction "OUT10_8") (pintype "passive"))
    )
    (net (code "41") (name "Net-(D17-K)") (class "Default")
      (node (ref "D17") (pin "2") (pinfunction "K_2") (pintype "passive"))
      (node (ref "U8") (pin "14") (pinfunction "OUT16_14") (pintype "passive"))
    )
    (net (code "42") (name "Net-(D18-K)") (class "Default")
      (node (ref "D18") (pin "2") (pinfunction "K_2") (pintype "passive"))
      (node (ref "U8") (pin "3") (pinfunction "OUT5_3") (pintype "passive"))
    )
    (net (code "43") (name "Net-(D19-K)") (class "Default")
      (node (ref "D19") (pin "2") (pinfunction "K_2") (pintype "passive"))
      (node (ref "U8") (pin "9") (pinfunction "OUT11_9") (pintype "passive"))
    )
    (net (code "44") (name "Net-(D20-K)") (class "Default")
      (node (ref "D20") (pin "2") (pinfunction "K_2") (pintype "passive"))
      (node (ref "U8") (pin "15") (pinfunction "OUT17_15") (pintype "passive"))
    )
    (net (code "45") (name "Net-(D21-K)") (class "Default")
      (node (ref "D21") (pin "2") (pinfunction "K_2") (pintype "passive"))
      (node (ref "U8") (pin "4") (pinfunction "OUT6_4") (pintype "passive"))
    )
    (net (code "46") (name "Net-(D22-K)") (class "Default")
      (node (ref "D22") (pin "2") (pinfunction "K_2") (pintype "passive"))
      (node (ref "U8") (pin "10") (pinfunction "OUT12_10") (pintype "passive"))
    )
    (net (code "47") (name "Net-(D23-K)") (class "Default")
      (node (ref "D23") (pin "2") (pinfunction "K_2") (pintype "passive"))
      (node (ref "U8") (pin "16") (pinfunction "OUT18_16") (pintype "passive"))
    )
    (net (code "48") (name "Net-(D24-K)") (class "Default")
      (node (ref "D24") (pin "2") (pinfunction "K_2") (pintype "passive"))
      (node (ref "U8") (pin "18") (pinfunction "OUT19_18") (pintype "passive"))
    )
    (net (code "49") (name "Net-(D25-K)") (class "Default")
      (node (ref "D25") (pin "2") (pinfunction "K_2") (pintype "passive"))
      (node (ref "U8") (pin "24") (pinfunction "OUT25_24") (pintype "passive"))
    )
    (net (code "50") (name "Net-(D26-K)") (class "Default")
      (node (ref "D26") (pin "2") (pinfunction "K_2") (pintype "passive"))
      (node (ref "U8") (pin "30") (pinfunction "OUT31_30") (pintype "passive"))
    )
    (net (code "51") (name "Net-(D27-K)") (class "Default")
      (node (ref "D27") (pin "2") (pinfunction "K_2") (pintype "passive"))
      (node (ref "U8") (pin "19") (pinfunction "OUT20_19") (pintype "passive"))
    )
    (net (code "52") (name "Net-(D28-K)") (class "Default")
      (node (ref "D28") (pin "2") (pinfunction "K_2") (pintype "passive"))
      (node (ref "U8") (pin "25") (pinfunction "OUT26_25") (pintype "passive"))
    )
    (net (code "53") (name "Net-(D29-K)") (class "Default")
      (node (ref "D29") (pin "2") (pinfunction "K_2") (pintype "passive"))
      (node (ref "U8") (pin "31") (pinfunction "OUT32_31") (pintype "passive"))
    )
    (net (code "54") (name "Net-(D30-K)") (class "Default")
      (node (ref "D30") (pin "2") (pinfunction "K_2") (pintype "passive"))
      (node (ref "U8") (pin "20") (pinfunction "OUT21_20") (pintype "passive"))
    )
    (net (code "55") (name "Net-(D31-K)") (class "Default")
      (node (ref "D31") (pin "2") (pinfunction "K_2") (pintype "passive"))
      (node (ref "U8") (pin "26") (pinfunction "OUT27_26") (pintype "passive"))
    )
    (net (code "56") (name "Net-(D32-K)") (class "Default")
      (node (ref "D32") (pin "2") (pinfunction "K_2") (pintype "passive"))
      (node (ref "U8") (pin "32") (pinfunction "OUT33_32") (pintype "passive"))
    )
    (net (code "57") (name "Net-(D33-A)") (class "Default")
      (node (ref "D33") (pin "1") (pinfunction "A_1") (pintype "passive"))
      (node (ref "R31") (pin "1") (pinfunction "1_1") (pintype "passive"))
    )
    (net (code "58") (name "Net-(D33-K)") (class "Default")
      (node (ref "D33") (pin "2") (pinfunction "K_2") (pintype "passive"))
      (node (ref "U10") (pin "3") (pinfunction "PC15-OSC32_OUT_3") (pintype "bidirectional"))
    )
    (net (code "59") (name "Net-(D34-K)") (class "Default")
      (node (ref "D34") (pin "2") (pinfunction "K_2") (pintype "passive"))
      (node (ref "U8") (pin "21") (pinfunction "OUT22_21") (pintype "passive"))
    )
    (net (code "60") (name "Net-(D35-K)") (class "Default")
      (node (ref "D35") (pin "2") (pinfunction "K_2") (pintype "passive"))
      (node (ref "U8") (pin "27") (pinfunction "OUT28_27") (pintype "passive"))
    )
    (net (code "61") (name "Net-(D36-K)") (class "Default")
      (node (ref "D36") (pin "2") (pinfunction "K_2") (pintype "passive"))
      (node (ref "U8") (pin "33") (pinfunction "OUT34_33") (pintype "passive"))
    )
    (net (code "62") (name "Net-(D37-K)") (class "Default")
      (node (ref "D37") (pin "2") (pinfunction "K_2") (pintype "passive"))
      (node (ref "U8") (pin "22") (pinfunction "OUT23_22") (pintype "passive"))
    )
    (net (code "63") (name "Net-(D38-K)") (class "Default")
      (node (ref "D38") (pin "2") (pinfunction "K_2") (pintype "passive"))
      (node (ref "U8") (pin "28") (pinfunction "OUT29_28") (pintype "passive"))
    )
    (net (code "64") (name "Net-(D39-K)") (class "Default")
      (node (ref "D39") (pin "2") (pinfunction "K_2") (pintype "passive"))
      (node (ref "U8") (pin "34") (pinfunction "OUT35_34") (pintype "passive"))
    )
    (net (code "65") (name "Net-(D40-K)") (class "Default")
      (node (ref "D40") (pin "2") (pinfunction "K_2") (pintype "passive"))
      (node (ref "U8") (pin "23") (pinfunction "OUT24_23") (pintype "passive"))
    )
    (net (code "66") (name "Net-(D41-K)") (class "Default")
      (node (ref "D41") (pin "2") (pinfunction "K_2") (pintype "passive"))
      (node (ref "U8") (pin "29") (pinfunction "OUT30_29") (pintype "passive"))
    )
    (net (code "67") (name "Net-(D42-K)") (class "Default")
      (node (ref "D42") (pin "2") (pinfunction "K_2") (pintype "passive"))
      (node (ref "U8") (pin "35") (pinfunction "OUT36_35") (pintype "passive"))
    )
    (net (code "68") (name "Net-(J1-CC1)") (class "Default")
      (node (ref "J1") (pin "A5") (pinfunction "CC1_A5") (pintype "passive"))
      (node (ref "R11") (pin "2") (pinfunction "2_2") (pintype "passive"))
    )
    (net (code "69") (name "Net-(J1-CC2)") (class "Default")
      (node (ref "J1") (pin "B5") (pinfunction "CC2_B5") (pintype "passive"))
      (node (ref "R10") (pin "2") (pinfunction "2_2") (pintype "passive"))
    )
    (net (code "70") (name "Net-(J2-T)") (class "Default")
      (node (ref "J2") (pin "3") (pinfunction "T_3") (pintype "passive"))
      (node (ref "R7") (pin "1") (pinfunction "1_1") (pintype "passive"))
    )
    (net (code "71") (name "Net-(J5-Pad5)") (class "Default")
      (node (ref "J5") (pin "5") (pinfunction "5_5") (pintype "passive"))
      (node (ref "JP1") (pin "1") (pinfunction "1_1") (pintype "passive"))
    )
    (net (code "72") (name "Net-(Q1-D)") (class "Default")
      (node (ref "Q1") (pin "2") (pinfunction "D_2") (pintype "passive"))
      (node (ref "R2") (pin "1") (pinfunction "1_1") (pintype "passive"))
    )
    (net (code "73") (name "Net-(Q2-G)") (class "Default")
      (node (ref "Q2") (pin "1") (pinfunction "G_1") (pintype "passive"))
      (node (ref "U1") (pin "4") (pinfunction "DO_4") (pintype "passive"))
    )
    (net (code "74") (name "Net-(Q3-G)") (class "Default")
      (node (ref "Q3") (pin "1") (pinfunction "G_1") (pintype "passive"))
      (node (ref "U1") (pin "5") (pinfunction "CO_5") (pintype "passive"))
    )
    (net (code "75") (name "Net-(Q4-D)") (class "Default")
      (node (ref "Q4") (pin "2") (pinfunction "D_2") (pintype "passive"))
      (node (ref "R13") (pin "2") (pinfunction "2_2") (pintype "passive"))
    )
    (net (code "76") (name "Net-(Q6-D)") (class "Default")
      (node (ref "C16") (pin "2") (pinfunction "2_2") (pintype "passive"))
      (node (ref "Q6") (pin "2") (pinfunction "D_2") (pintype "passive"))
      (node (ref "U7") (pin "1") (pinfunction "VIN_1") (pintype "passive"))
      (node (ref "U7") (pin "3") (pinfunction "EN_3") (pintype "passive"))
    )
    (net (code "77") (name "Net-(Q6-G)") (class "Default")
      (node (ref "Q6") (pin "1") (pinfunction "G_1") (pintype "passive"))
      (node (ref "R18") (pin "1") (pinfunction "1_1") (pintype "passive"))
      (node (ref "S1") (pin "2") (pinfunction "COM_2") (pintype "passive"))
    )
    (net (code "78") (name "Net-(S1-A)") (class "Default")
      (node (ref "R20") (pin "1") (pinfunction "1_1") (pintype "passive"))
      (node (ref "S1") (pin "1") (pinfunction "A_1") (pintype "passive"))
    )
    (net (code "79") (name "Net-(S1-B)") (class "Default")
      (node (ref "R21") (pin "1") (pinfunction "1_1") (pintype "passive"))
      (node (ref "S1") (pin "3") (pinfunction "B_3") (pintype "passive"))
    )
    (net (code "80") (name "Net-(U1-VDD)") (class "Default")
      (node (ref "C2") (pin "2") (pinfunction "2_2") (pintype "passive"))
      (node (ref "R1") (pin "2") (pinfunction "2_2") (pintype "passive"))
      (node (ref "U1") (pin "2") (pinfunction "VDD_2") (pintype "passive"))
    )
    (net (code "81") (name "Net-(U1-VM)") (class "Default")
      (node (ref "R3") (pin "1") (pinfunction "1_1") (pintype "passive"))
      (node (ref "U1") (pin "1") (pinfunction "VM_1") (pintype "passive"))
    )
    (net (code "82") (name "Net-(U2-AUDIO_IN)") (class "Default")
      (node (ref "C3") (pin "1") (pinfunction "1_1") (pintype "passive"))
      (node (ref "U2") (pin "5") (pinfunction "AUDIO_IN_5") (pintype "passive"))
    )
    (net (code "83") (name "Net-(U2-CKIN)") (class "Default")
      (node (ref "C8") (pin "2") (pinfunction "2_2") (pintype "passive"))
      (node (ref "R9") (pin "2") (pinfunction "2_2") (pintype "passive"))
      (node (ref "U2") (pin "8") (pinfunction "CKIN_8") (pintype "passive"))
    )
    (net (code "84") (name "Net-(U2-GNDREF)") (class "Default")
      (node (ref "C7") (pin "2") (pinfunction "2_2") (pintype "passive"))
      (node (ref "U2") (pin "6") (pinfunction "GNDREF_6") (pintype "power_in"))
    )
    (net (code "85") (name "Net-(U3A-+)") (class "Default")
      (node (ref "C12") (pin "2") (pinfunction "2_2") (pintype "passive"))
      (node (ref "R16") (pin "2") (pinfunction "2_2") (pintype "passive"))
      (node (ref "U3") (pin "3") (pinfunction "+_3") (pintype "passive"))
    )
    (net (code "86") (name "Net-(U3A--)") (class "Default")
      (node (ref "U3") (pin "1") (pinfunction "OUT_1") (pintype "passive"))
      (node (ref "U3") (pin "2") (pinfunction "-_2") (pintype "passive"))
      (node (ref "U5") (pin "2") (pinfunction "IN+_2") (pintype "passive"))
    )
    (net (code "87") (name "Net-(U3B-+)") (class "Default")
      (node (ref "R12") (pin "2") (pinfunction "2_2") (pintype "passive"))
      (node (ref "R8") (pin "2") (pinfunction "2_2") (pintype "passive"))
      (node (ref "U3") (pin "5") (pinfunction "+_5") (pintype "passive"))
    )
    (net (code "88") (name "Net-(U3B--)") (class "Default")
      (node (ref "R2") (pin "2") (pinfunction "2_2") (pintype "passive"))
      (node (ref "R5") (pin "2") (pinfunction "2_2") (pintype "passive"))
      (node (ref "R6") (pin "1") (pinfunction "1_1") (pintype "passive"))
      (node (ref "U3") (pin "6") (pinfunction "-_6") (pintype "passive"))
    )
    (net (code "89") (name "Net-(U3B-OUT)") (class "Default")
      (node (ref "C3") (pin "2") (pinfunction "2_2") (pintype "passive"))
      (node (ref "R6") (pin "2") (pinfunction "2_2") (pintype "passive"))
      (node (ref "U3") (pin "7") (pinfunction "OUT_7") (pintype "passive"))
    )
    (net (code "90") (name "Net-(U6-REF)") (class "Default")
      (node (ref "R15") (pin "2") (pinfunction "2_2") (pintype "passive"))
      (node (ref "R17") (pin "1") (pinfunction "1_1") (pintype "passive"))
      (node (ref "U6") (pin "2") (pinfunction "REF_2") (pintype "passive"))
    )
    (net (code "91") (name "Net-(U8A-R_EXT)") (class "Default")
      (node (ref "R25") (pin "1") (pinfunction "1_1") (pintype "passive"))
      (node (ref "U8") (pin "40") (pinfunction "R_EXT_40") (pintype "passive"))
    )
    (net (code "92") (name "Net-(U9-PROG)") (class "Default")
      (node (ref "R30") (pin "1") (pinfunction "1_1") (pintype "passive"))
      (node (ref "U9") (pin "6") (pinfunction "PROG_6") (pintype "output"))
    )
    (net (code "93") (name "Net-(U9-THERM)") (class "Default")
      (node (ref "R29") (pin "2") (pinfunction "2_2") (pintype "passive"))
      (node (ref "U9") (pin "8") (pinfunction "THERM_8") (pintype "input"))
    )
    (net (code "94") (name "Net-(U10-PB9{slash}PC14-OSC32_IN)") (class "Default")
      (node (ref "U10") (pin "2") (pinfunction "PB9/PC14-OSC32_IN_2") (pintype "bidirectional"))
      (node (ref "Y1") (pin "3") (pinfunction "OUT_3") (pintype "passive"))
    )
    (net (code "95") (name "USB_N") (class "Default")
      (node (ref "J1") (pin "A7") (pinfunction "D-_A7") (pintype "passive"))
      (node (ref "J1") (pin "B7") (pinfunction "D-_B7") (pintype "passive"))
      (node (ref "R4") (pin "1") (pinfunction "1_1") (pintype "passive"))
    )
    (net (code "96") (name "USB_P") (class "Default")
      (node (ref "J1") (pin "A6") (pinfunction "D+_A6") (pintype "passive"))
      (node (ref "J1") (pin "B6") (pinfunction "D+_B6") (pintype "passive"))
      (node (ref "R4") (pin "2") (pinfunction "2_2") (pintype "passive"))
    )
    (net (code "97") (name "VBAT") (class "Default")
      (node (ref "C23") (pin "2") (pinfunction "2_2") (pintype "passive"))
      (node (ref "J3") (pin "1") (pinfunction "1_1") (pintype "passive"))
      (node (ref "Q5") (pin "2") (pinfunction "D_2") (pintype "passive"))
      (node (ref "R1") (pin "1") (pinfunction "1_1") (pintype "passive"))
      (node (ref "U9") (pin "10") (pinfunction "VBAT_10") (pintype "power_in"))
      (node (ref "U9") (pin "9") (pinfunction "VBAT_9") (pintype "power_in"))
    )
    (net (code "98") (name "VBUS") (class "Default")
      (node (ref "C1") (pin "2") (pinfunction "2_2") (pintype "passive"))
      (node (ref "C22") (pin "2") (pinfunction "2_2") (pintype "passive"))
      (node (ref "D2") (pin "1") (pinfunction "A_1") (pintype "passive"))
      (node (ref "J1") (pin "A4_B9") (pinfunction "VBUS_A4_B9") (pintype "passive"))
      (node (ref "J1") (pin "B4_A9") (pinfunction "VBUS_B4_A9") (pintype "passive"))
      (node (ref "Q5") (pin "1") (pinfunction "G_1") (pintype "passive"))
      (node (ref "R19") (pin "2") (pinfunction "2_2") (pintype "passive"))
      (node (ref "R26") (pin "1") (pinfunction "1_1") (pintype "passive"))
      (node (ref "R27") (pin "1") (pinfunction "1_1") (pintype "passive"))
      (node (ref "R28") (pin "1") (pinfunction "1_1") (pintype "passive"))
      (node (ref "U9") (pin "1") (pinfunction "VDD_1") (pintype "power_in"))
      (node (ref "U9") (pin "2") (pinfunction "VDD_2") (pintype "power_in"))
    )
    (net (code "99") (name "unconnected-(J2-R-Pad2)") (class "Default")
      (node (ref "J2") (pin "2") (pinfunction "R_2") (pintype "passive+no_connect"))
    )
    (net (code "100") (name "unconnected-(J3-PadS1)") (class "Default")
      (node (ref "J3") (pin "S1") (pinfunction "S1_S1") (pintype "passive+no_connect"))
    )
    (net (code "101") (name "unconnected-(J3-PadS2)") (class "Default")
      (node (ref "J3") (pin "S2") (pinfunction "S2_S2") (pintype "passive+no_connect"))
    )
    (net (code "102") (name "unconnected-(J5-Pad7)") (class "Default")
      (node (ref "J5") (pin "7") (pinfunction "7_7") (pintype "passive+no_connect"))
    )
    (net (code "103") (name "unconnected-(J5-Pad8)") (class "Default")
      (node (ref "J5") (pin "8") (pinfunction "8_8") (pintype "passive+no_connect"))
    )
    (net (code "104") (name "unconnected-(J5-Pad9)") (class "Default")
      (node (ref "J5") (pin "9") (pinfunction "9_9") (pintype "passive+no_connect"))
    )
    (net (code "105") (name "unconnected-(S1-S1-Pad4)") (class "Default")
      (node (ref "S1") (pin "4") (pinfunction "S1_4") (pintype "passive+no_connect"))
    )
    (net (code "106") (name "unconnected-(S1-S2-Pad5)") (class "Default")
      (node (ref "S1") (pin "5") (pinfunction "S2_5") (pintype "passive+no_connect"))
    )
    (net (code "107") (name "unconnected-(U10-PA11{slash}PA9-Pad16)") (class "Default")
      (node (ref "U10") (pin "16") (pinfunction "PA11/PA9_16") (pintype "bidirectional+no_connect"))
    )
    (net (code "108") (name "unconnected-(U10-PA12{slash}PA10-Pad17)") (class "Default")
      (node (ref "U10") (pin "17") (pinfunction "PA12/PA10_17") (pintype "bidirectional+no_connect"))
    )
    (net (code "109") (name "unconnected-(U10-PB0{slash}PB1{slash}PB2{slash}PA8-Pad15)") (class "Default")
      (node (ref "U10") (pin "15") (pinfunction "PB0/PB1/PB2/PA8_15") (pintype "bidirectional+no_connect"))
    )
    (net (code "110") (name "unconnected-(Y1-E{slash}D-Pad1)") (class "Default")
      (node (ref "Y1") (pin "1") (pinfunction "E/D_1") (pintype "passive+no_connect"))
    )
  )
)
